# 56_ch_sample-and-hold_card_v1_0.net
KiCad netlist of a schematic drawn in EAGLE
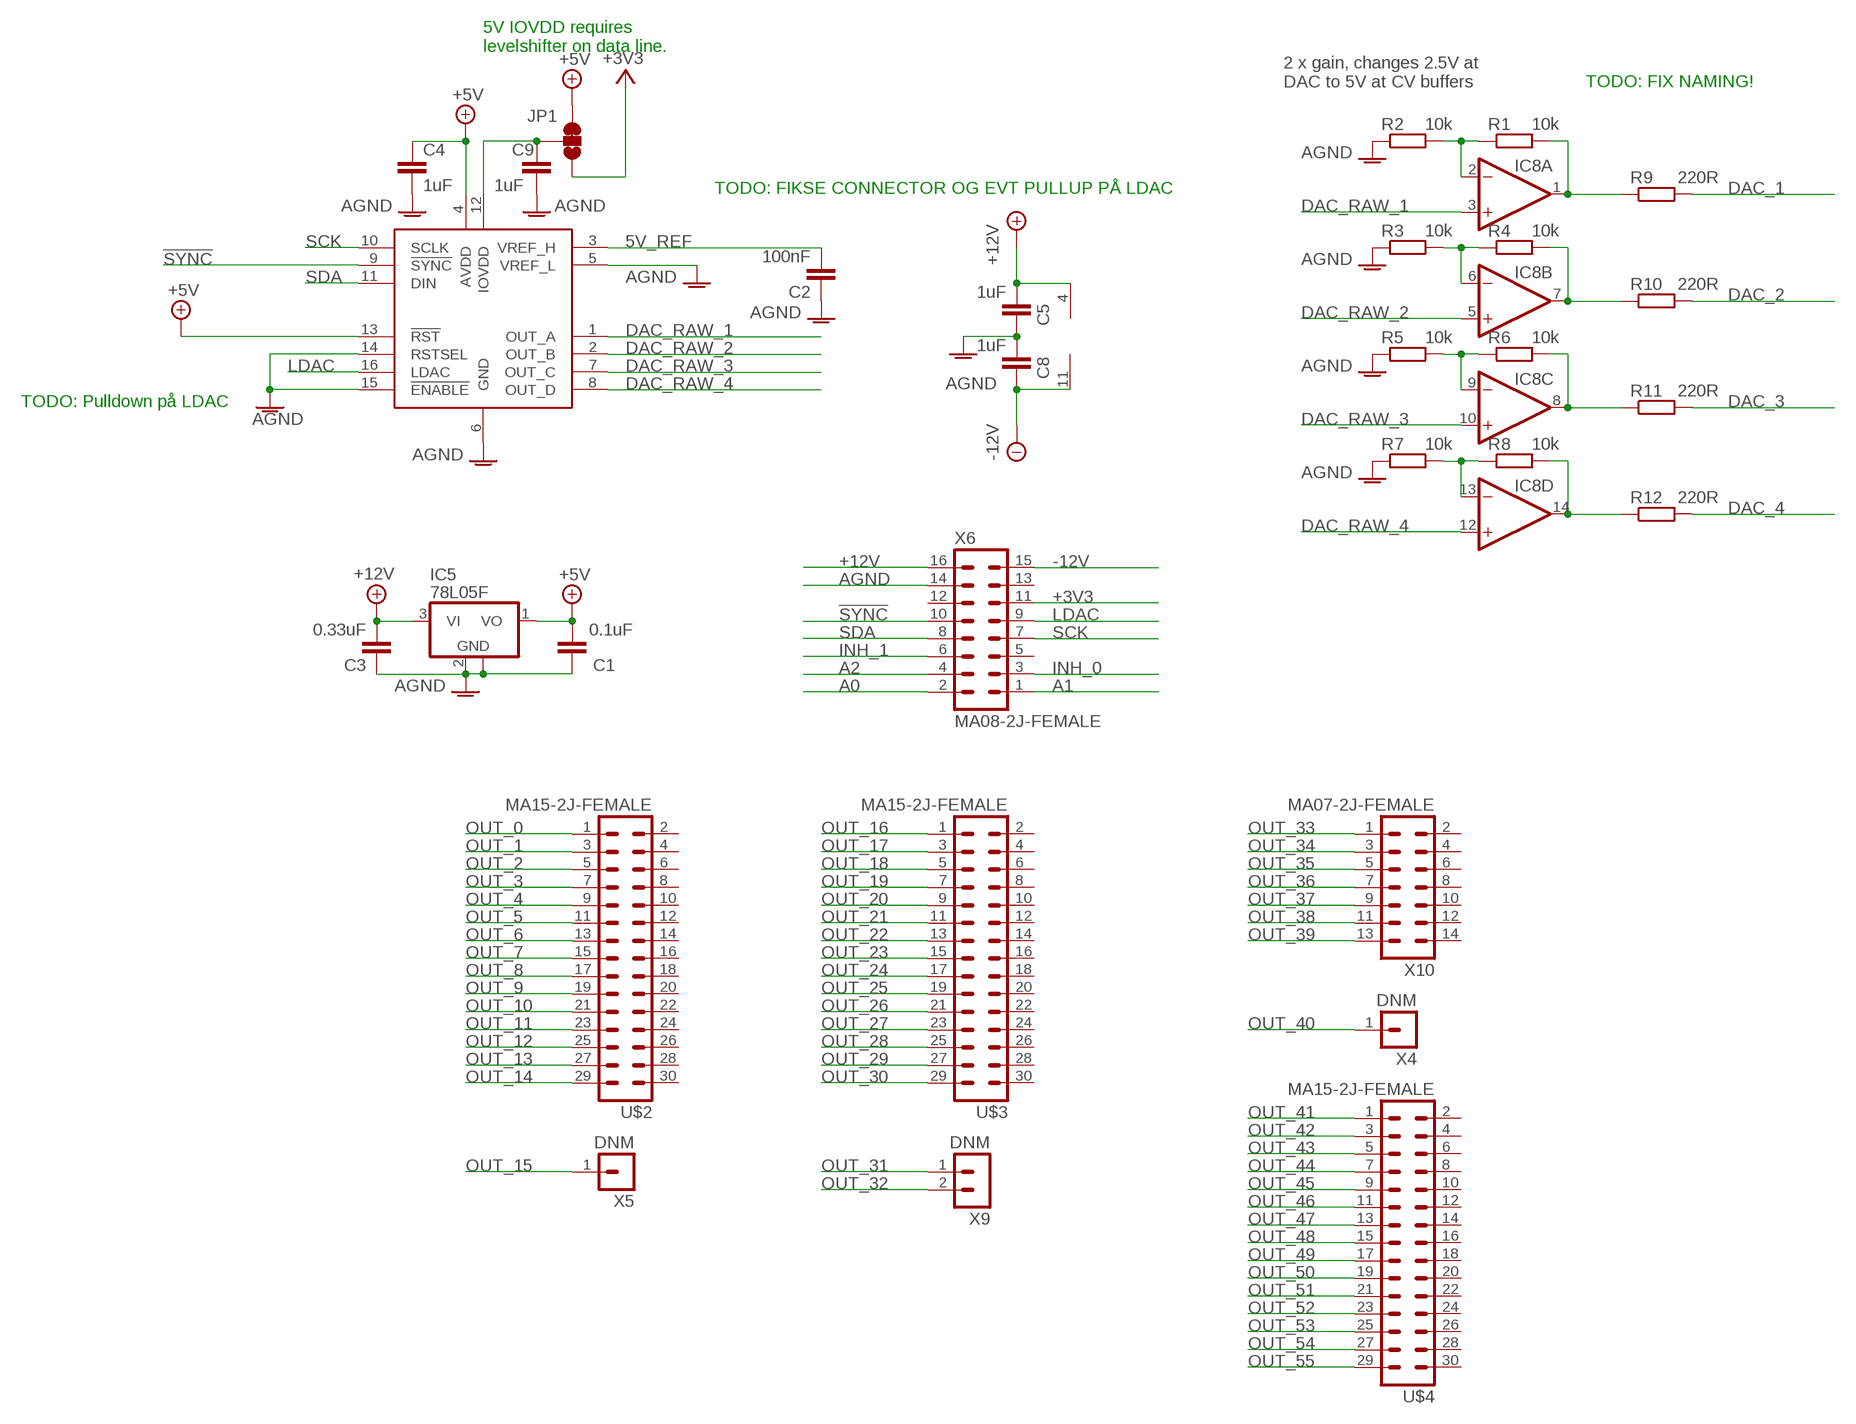
[diagram p0: schematic, sheet 1]
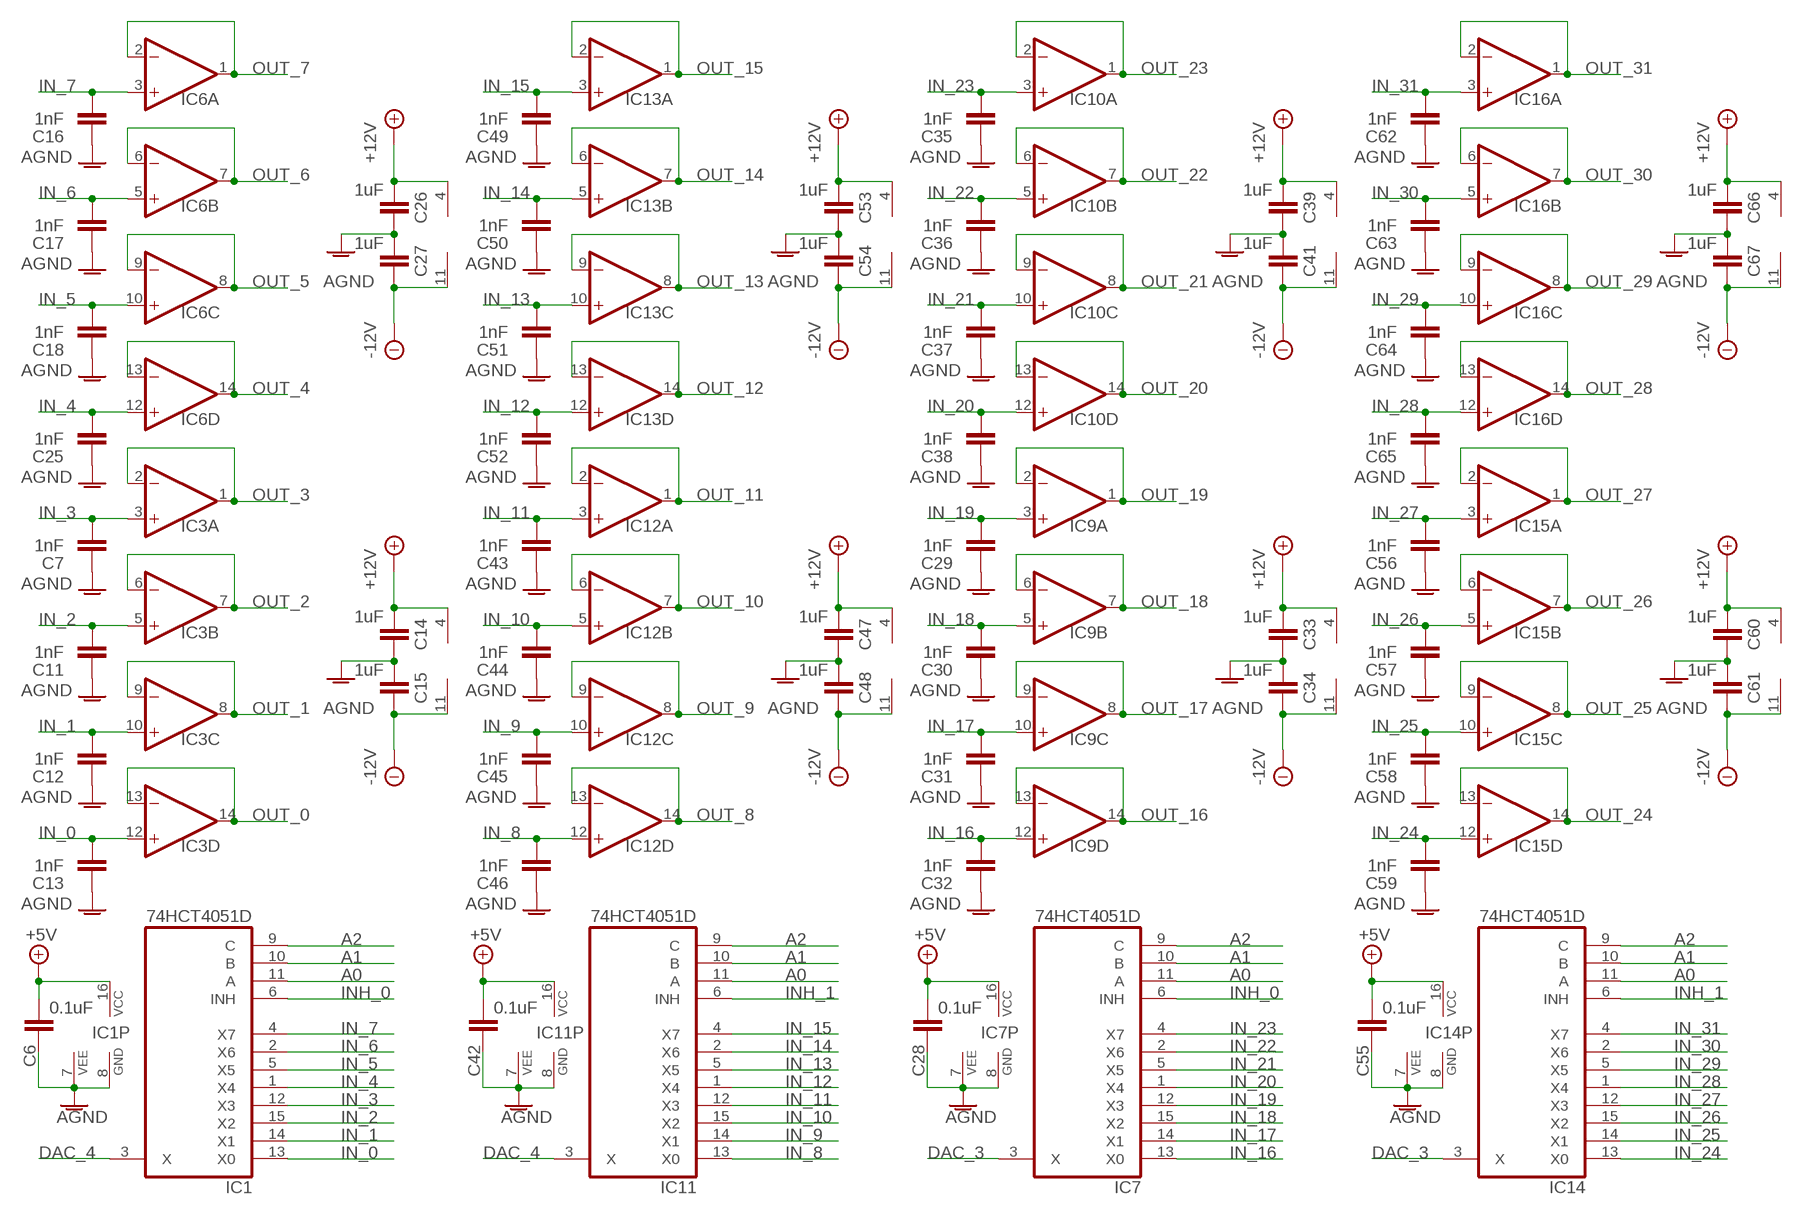
[diagram p1: schematic, sheet 2]
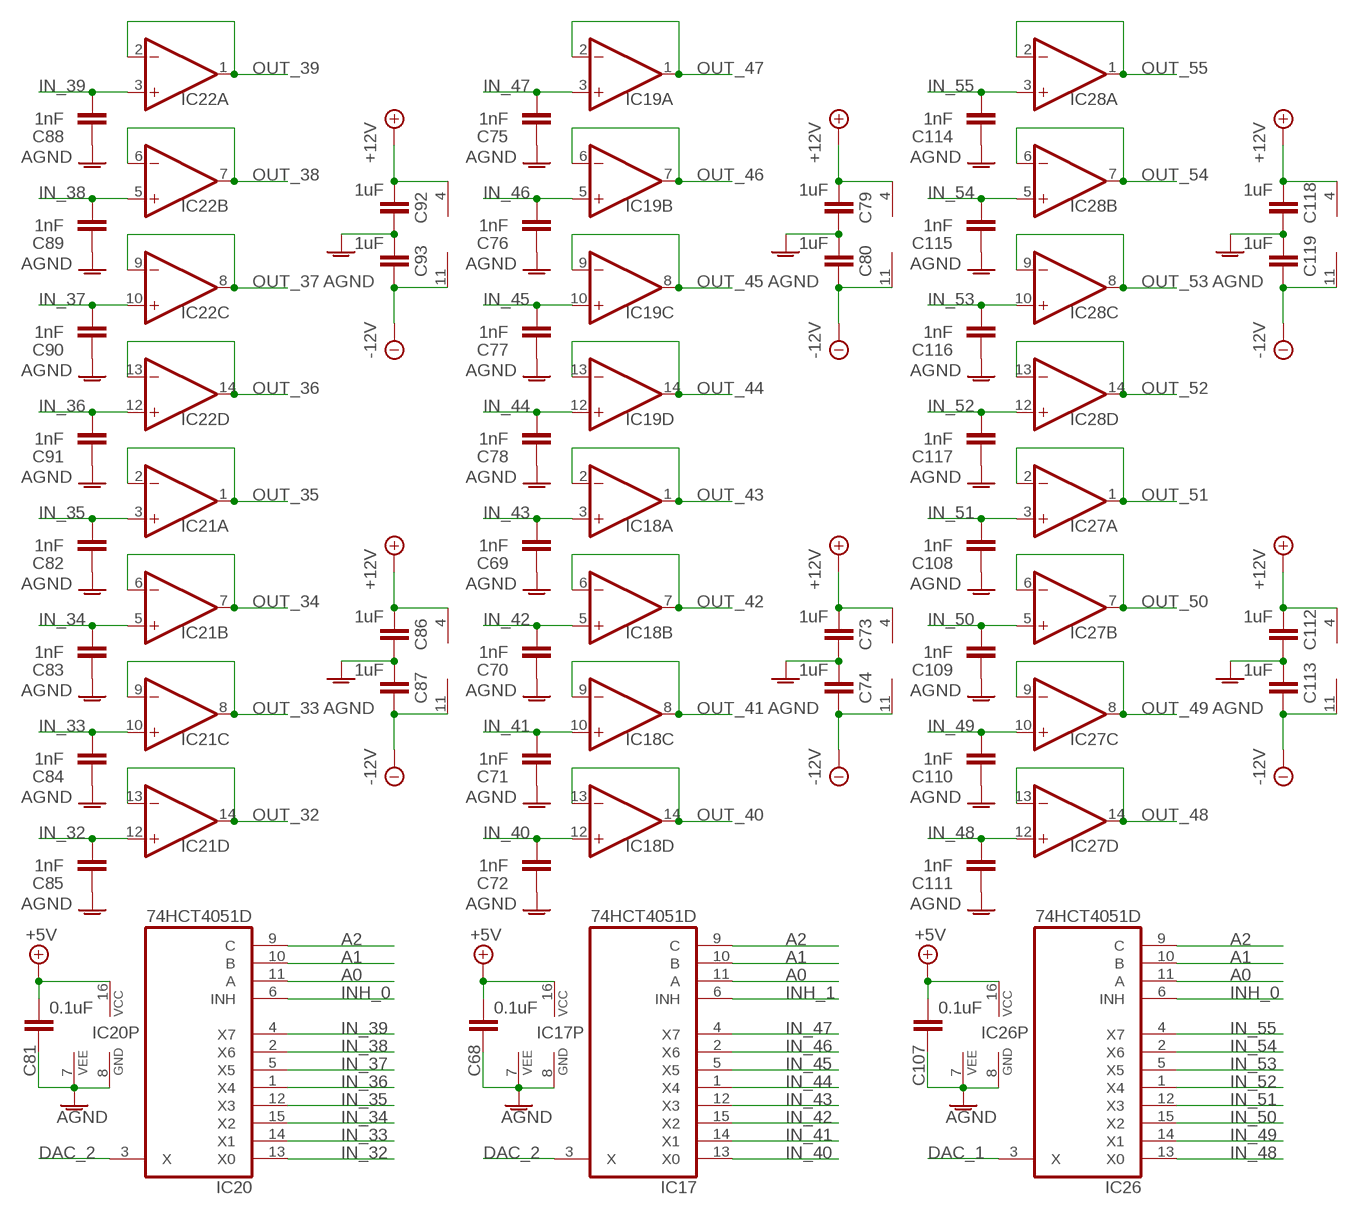
[diagram p2: schematic, sheet 3]

(export (version "E")
  (design (tool "Eeschema 10.0.6"))
  (components
    (comp (ref "C68")
      (value "0.1uF")
      (footprint "eagle-import:C0402-J")
      (libsource (lib "eagle-import") (part "C-EU-J0402"))
    )
    (comp (ref "C69")
      (value "1nF")
      (footprint "eagle-import:C0603-J")
      (libsource (lib "eagle-import") (part "C-EU-J0603"))
    )
    (comp (ref "C70")
      (value "1nF")
      (footprint "eagle-import:C0603-J")
      (libsource (lib "eagle-import") (part "C-EU-J0603"))
    )
    (comp (ref "C71")
      (value "1nF")
      (footprint "eagle-import:C0603-J")
      (libsource (lib "eagle-import") (part "C-EU-J0603"))
    )
    (comp (ref "C72")
      (value "1nF")
      (footprint "eagle-import:C0603-J")
      (libsource (lib "eagle-import") (part "C-EU-J0603"))
    )
    (comp (ref "C73")
      (value "1uF")
      (footprint "eagle-import:C0402-J")
      (libsource (lib "eagle-import") (part "C-EU-J0402"))
    )
    (comp (ref "C74")
      (value "1uF")
      (footprint "eagle-import:C0402-J")
      (libsource (lib "eagle-import") (part "C-EU-J0402"))
    )
    (comp (ref "C75")
      (value "1nF")
      (footprint "eagle-import:C0603-J")
      (libsource (lib "eagle-import") (part "C-EU-J0603"))
    )
    (comp (ref "C76")
      (value "1nF")
      (footprint "eagle-import:C0603-J")
      (libsource (lib "eagle-import") (part "C-EU-J0603"))
    )
    (comp (ref "C77")
      (value "1nF")
      (footprint "eagle-import:C0603-J")
      (libsource (lib "eagle-import") (part "C-EU-J0603"))
    )
    (comp (ref "C78")
      (value "1nF")
      (footprint "eagle-import:C0603-J")
      (libsource (lib "eagle-import") (part "C-EU-J0603"))
    )
    (comp (ref "C79")
      (value "1uF")
      (footprint "eagle-import:C0402-J")
      (libsource (lib "eagle-import") (part "C-EU-J0402"))
    )
    (comp (ref "C80")
      (value "1uF")
      (footprint "eagle-import:C0402-J")
      (libsource (lib "eagle-import") (part "C-EU-J0402"))
    )
    (comp (ref "C81")
      (value "0.1uF")
      (footprint "eagle-import:C0402-J")
      (libsource (lib "eagle-import") (part "C-EU-J0402"))
    )
    (comp (ref "C82")
      (value "1nF")
      (footprint "eagle-import:C0603-J")
      (libsource (lib "eagle-import") (part "C-EU-J0603"))
    )
    (comp (ref "C83")
      (value "1nF")
      (footprint "eagle-import:C0603-J")
      (libsource (lib "eagle-import") (part "C-EU-J0603"))
    )
    (comp (ref "C84")
      (value "1nF")
      (footprint "eagle-import:C0603-J")
      (libsource (lib "eagle-import") (part "C-EU-J0603"))
    )
    (comp (ref "C85")
      (value "1nF")
      (footprint "eagle-import:C0603-J")
      (libsource (lib "eagle-import") (part "C-EU-J0603"))
    )
    (comp (ref "C86")
      (value "1uF")
      (footprint "eagle-import:C0402-J")
      (libsource (lib "eagle-import") (part "C-EU-J0402"))
    )
    (comp (ref "C87")
      (value "1uF")
      (footprint "eagle-import:C0402-J")
      (libsource (lib "eagle-import") (part "C-EU-J0402"))
    )
    (comp (ref "C88")
      (value "1nF")
      (footprint "eagle-import:C0603-J")
      (libsource (lib "eagle-import") (part "C-EU-J0603"))
    )
    (comp (ref "C89")
      (value "1nF")
      (footprint "eagle-import:C0603-J")
      (libsource (lib "eagle-import") (part "C-EU-J0603"))
    )
    (comp (ref "C90")
      (value "1nF")
      (footprint "eagle-import:C0603-J")
      (libsource (lib "eagle-import") (part "C-EU-J0603"))
    )
    (comp (ref "C91")
      (value "1nF")
      (footprint "eagle-import:C0603-J")
      (libsource (lib "eagle-import") (part "C-EU-J0603"))
    )
    (comp (ref "C92")
      (value "1uF")
      (footprint "eagle-import:C0402-J")
      (libsource (lib "eagle-import") (part "C-EU-J0402"))
    )
    (comp (ref "C93")
      (value "1uF")
      (footprint "eagle-import:C0402-J")
      (libsource (lib "eagle-import") (part "C-EU-J0402"))
    )
    (comp (ref "C107")
      (value "0.1uF")
      (footprint "eagle-import:C0402-J")
      (libsource (lib "eagle-import") (part "C-EU-J0402"))
    )
    (comp (ref "C108")
      (value "1nF")
      (footprint "eagle-import:C0603-J")
      (libsource (lib "eagle-import") (part "C-EU-J0603"))
    )
    (comp (ref "C109")
      (value "1nF")
      (footprint "eagle-import:C0603-J")
      (libsource (lib "eagle-import") (part "C-EU-J0603"))
    )
    (comp (ref "C110")
      (value "1nF")
      (footprint "eagle-import:C0603-J")
      (libsource (lib "eagle-import") (part "C-EU-J0603"))
    )
    (comp (ref "C111")
      (value "1nF")
      (footprint "eagle-import:C0603-J")
      (libsource (lib "eagle-import") (part "C-EU-J0603"))
    )
    (comp (ref "C112")
      (value "1uF")
      (footprint "eagle-import:C0402-J")
      (libsource (lib "eagle-import") (part "C-EU-J0402"))
    )
    (comp (ref "C113")
      (value "1uF")
      (footprint "eagle-import:C0402-J")
      (libsource (lib "eagle-import") (part "C-EU-J0402"))
    )
    (comp (ref "C114")
      (value "1nF")
      (footprint "eagle-import:C0603-J")
      (libsource (lib "eagle-import") (part "C-EU-J0603"))
    )
    (comp (ref "C115")
      (value "1nF")
      (footprint "eagle-import:C0603-J")
      (libsource (lib "eagle-import") (part "C-EU-J0603"))
    )
    (comp (ref "C116")
      (value "1nF")
      (footprint "eagle-import:C0603-J")
      (libsource (lib "eagle-import") (part "C-EU-J0603"))
    )
    (comp (ref "C117")
      (value "1nF")
      (footprint "eagle-import:C0603-J")
      (libsource (lib "eagle-import") (part "C-EU-J0603"))
    )
    (comp (ref "C118")
      (value "1uF")
      (footprint "eagle-import:C0402-J")
      (libsource (lib "eagle-import") (part "C-EU-J0402"))
    )
    (comp (ref "C119")
      (value "1uF")
      (footprint "eagle-import:C0402-J")
      (libsource (lib "eagle-import") (part "C-EU-J0402"))
    )
    (comp (ref "IC17")
      (value "74HCT4051D")
      (footprint "eagle-import:SO16")
      (libsource (lib "eagle-import") (part "4051D"))
    )
    (comp (ref "IC18")
      (value "TL074JT")
      (footprint "eagle-import:TSSOP14J")
      (libsource (lib "eagle-import") (part "TL074JT"))
    )
    (comp (ref "IC19")
      (value "TL074JT")
      (footprint "eagle-import:TSSOP14J")
      (libsource (lib "eagle-import") (part "TL074JT"))
    )
    (comp (ref "IC20")
      (value "74HCT4051D")
      (footprint "eagle-import:SO16")
      (libsource (lib "eagle-import") (part "4051D"))
    )
    (comp (ref "IC21")
      (value "TL074JT")
      (footprint "eagle-import:TSSOP14J")
      (libsource (lib "eagle-import") (part "TL074JT"))
    )
    (comp (ref "IC22")
      (value "TL074JT")
      (footprint "eagle-import:TSSOP14J")
      (libsource (lib "eagle-import") (part "TL074JT"))
    )
    (comp (ref "IC26")
      (value "74HCT4051D")
      (footprint "eagle-import:SO16")
      (libsource (lib "eagle-import") (part "4051D"))
    )
    (comp (ref "IC27")
      (value "TL074JT")
      (footprint "eagle-import:TSSOP14J")
      (libsource (lib "eagle-import") (part "TL074JT"))
    )
    (comp (ref "IC28")
      (value "TL074JT")
      (footprint "eagle-import:TSSOP14J")
      (libsource (lib "eagle-import") (part "TL074JT"))
    )
    (comp (ref "C6")
      (value "0.1uF")
      (footprint "eagle-import:C0402-J")
      (libsource (lib "eagle-import") (part "C-EU-J0402"))
    )
    (comp (ref "C7")
      (value "1nF")
      (footprint "eagle-import:C0603-J")
      (libsource (lib "eagle-import") (part "C-EU-J0603"))
    )
    (comp (ref "C11")
      (value "1nF")
      (footprint "eagle-import:C0603-J")
      (libsource (lib "eagle-import") (part "C-EU-J0603"))
    )
    (comp (ref "C12")
      (value "1nF")
      (footprint "eagle-import:C0603-J")
      (libsource (lib "eagle-import") (part "C-EU-J0603"))
    )
    (comp (ref "C13")
      (value "1nF")
      (footprint "eagle-import:C0603-J")
      (libsource (lib "eagle-import") (part "C-EU-J0603"))
    )
    (comp (ref "C14")
      (value "1uF")
      (footprint "eagle-import:C0402-J")
      (libsource (lib "eagle-import") (part "C-EU-J0402"))
    )
    (comp (ref "C15")
      (value "1uF")
      (footprint "eagle-import:C0402-J")
      (libsource (lib "eagle-import") (part "C-EU-J0402"))
    )
    (comp (ref "C16")
      (value "1nF")
      (footprint "eagle-import:C0603-J")
      (libsource (lib "eagle-import") (part "C-EU-J0603"))
    )
    (comp (ref "C17")
      (value "1nF")
      (footprint "eagle-import:C0603-J")
      (libsource (lib "eagle-import") (part "C-EU-J0603"))
    )
    (comp (ref "C18")
      (value "1nF")
      (footprint "eagle-import:C0603-J")
      (libsource (lib "eagle-import") (part "C-EU-J0603"))
    )
    (comp (ref "C25")
      (value "1nF")
      (footprint "eagle-import:C0603-J")
      (libsource (lib "eagle-import") (part "C-EU-J0603"))
    )
    (comp (ref "C26")
      (value "1uF")
      (footprint "eagle-import:C0402-J")
      (libsource (lib "eagle-import") (part "C-EU-J0402"))
    )
    (comp (ref "C27")
      (value "1uF")
      (footprint "eagle-import:C0402-J")
      (libsource (lib "eagle-import") (part "C-EU-J0402"))
    )
    (comp (ref "C28")
      (value "0.1uF")
      (footprint "eagle-import:C0402-J")
      (libsource (lib "eagle-import") (part "C-EU-J0402"))
    )
    (comp (ref "C29")
      (value "1nF")
      (footprint "eagle-import:C0603-J")
      (libsource (lib "eagle-import") (part "C-EU-J0603"))
    )
    (comp (ref "C30")
      (value "1nF")
      (footprint "eagle-import:C0603-J")
      (libsource (lib "eagle-import") (part "C-EU-J0603"))
    )
    (comp (ref "C31")
      (value "1nF")
      (footprint "eagle-import:C0603-J")
      (libsource (lib "eagle-import") (part "C-EU-J0603"))
    )
    (comp (ref "C32")
      (value "1nF")
      (footprint "eagle-import:C0603-J")
      (libsource (lib "eagle-import") (part "C-EU-J0603"))
    )
    (comp (ref "C33")
      (value "1uF")
      (footprint "eagle-import:C0402-J")
      (libsource (lib "eagle-import") (part "C-EU-J0402"))
    )
    (comp (ref "C34")
      (value "1uF")
      (footprint "eagle-import:C0402-J")
      (libsource (lib "eagle-import") (part "C-EU-J0402"))
    )
    (comp (ref "C35")
      (value "1nF")
      (footprint "eagle-import:C0603-J")
      (libsource (lib "eagle-import") (part "C-EU-J0603"))
    )
    (comp (ref "C36")
      (value "1nF")
      (footprint "eagle-import:C0603-J")
      (libsource (lib "eagle-import") (part "C-EU-J0603"))
    )
    (comp (ref "C37")
      (value "1nF")
      (footprint "eagle-import:C0603-J")
      (libsource (lib "eagle-import") (part "C-EU-J0603"))
    )
    (comp (ref "C38")
      (value "1nF")
      (footprint "eagle-import:C0603-J")
      (libsource (lib "eagle-import") (part "C-EU-J0603"))
    )
    (comp (ref "C39")
      (value "1uF")
      (footprint "eagle-import:C0402-J")
      (libsource (lib "eagle-import") (part "C-EU-J0402"))
    )
    (comp (ref "C41")
      (value "1uF")
      (footprint "eagle-import:C0402-J")
      (libsource (lib "eagle-import") (part "C-EU-J0402"))
    )
    (comp (ref "C42")
      (value "0.1uF")
      (footprint "eagle-import:C0402-J")
      (libsource (lib "eagle-import") (part "C-EU-J0402"))
    )
    (comp (ref "C43")
      (value "1nF")
      (footprint "eagle-import:C0603-J")
      (libsource (lib "eagle-import") (part "C-EU-J0603"))
    )
    (comp (ref "C44")
      (value "1nF")
      (footprint "eagle-import:C0603-J")
      (libsource (lib "eagle-import") (part "C-EU-J0603"))
    )
    (comp (ref "C45")
      (value "1nF")
      (footprint "eagle-import:C0603-J")
      (libsource (lib "eagle-import") (part "C-EU-J0603"))
    )
    (comp (ref "C46")
      (value "1nF")
      (footprint "eagle-import:C0603-J")
      (libsource (lib "eagle-import") (part "C-EU-J0603"))
    )
    (comp (ref "C47")
      (value "1uF")
      (footprint "eagle-import:C0402-J")
      (libsource (lib "eagle-import") (part "C-EU-J0402"))
    )
    (comp (ref "C48")
      (value "1uF")
      (footprint "eagle-import:C0402-J")
      (libsource (lib "eagle-import") (part "C-EU-J0402"))
    )
    (comp (ref "C49")
      (value "1nF")
      (footprint "eagle-import:C0603-J")
      (libsource (lib "eagle-import") (part "C-EU-J0603"))
    )
    (comp (ref "C50")
      (value "1nF")
      (footprint "eagle-import:C0603-J")
      (libsource (lib "eagle-import") (part "C-EU-J0603"))
    )
    (comp (ref "C51")
      (value "1nF")
      (footprint "eagle-import:C0603-J")
      (libsource (lib "eagle-import") (part "C-EU-J0603"))
    )
    (comp (ref "C52")
      (value "1nF")
      (footprint "eagle-import:C0603-J")
      (libsource (lib "eagle-import") (part "C-EU-J0603"))
    )
    (comp (ref "C53")
      (value "1uF")
      (footprint "eagle-import:C0402-J")
      (libsource (lib "eagle-import") (part "C-EU-J0402"))
    )
    (comp (ref "C54")
      (value "1uF")
      (footprint "eagle-import:C0402-J")
      (libsource (lib "eagle-import") (part "C-EU-J0402"))
    )
    (comp (ref "C55")
      (value "0.1uF")
      (footprint "eagle-import:C0402-J")
      (libsource (lib "eagle-import") (part "C-EU-J0402"))
    )
    (comp (ref "C56")
      (value "1nF")
      (footprint "eagle-import:C0603-J")
      (libsource (lib "eagle-import") (part "C-EU-J0603"))
    )
    (comp (ref "C57")
      (value "1nF")
      (footprint "eagle-import:C0603-J")
      (libsource (lib "eagle-import") (part "C-EU-J0603"))
    )
    (comp (ref "C58")
      (value "1nF")
      (footprint "eagle-import:C0603-J")
      (libsource (lib "eagle-import") (part "C-EU-J0603"))
    )
    (comp (ref "C59")
      (value "1nF")
      (footprint "eagle-import:C0603-J")
      (libsource (lib "eagle-import") (part "C-EU-J0603"))
    )
    (comp (ref "C60")
      (value "1uF")
      (footprint "eagle-import:C0402-J")
      (libsource (lib "eagle-import") (part "C-EU-J0402"))
    )
    (comp (ref "C61")
      (value "1uF")
      (footprint "eagle-import:C0402-J")
      (libsource (lib "eagle-import") (part "C-EU-J0402"))
    )
    (comp (ref "C62")
      (value "1nF")
      (footprint "eagle-import:C0603-J")
      (libsource (lib "eagle-import") (part "C-EU-J0603"))
    )
    (comp (ref "C63")
      (value "1nF")
      (footprint "eagle-import:C0603-J")
      (libsource (lib "eagle-import") (part "C-EU-J0603"))
    )
    (comp (ref "C64")
      (value "1nF")
      (footprint "eagle-import:C0603-J")
      (libsource (lib "eagle-import") (part "C-EU-J0603"))
    )
    (comp (ref "C65")
      (value "1nF")
      (footprint "eagle-import:C0603-J")
      (libsource (lib "eagle-import") (part "C-EU-J0603"))
    )
    (comp (ref "C66")
      (value "1uF")
      (footprint "eagle-import:C0402-J")
      (libsource (lib "eagle-import") (part "C-EU-J0402"))
    )
    (comp (ref "C67")
      (value "1uF")
      (footprint "eagle-import:C0402-J")
      (libsource (lib "eagle-import") (part "C-EU-J0402"))
    )
    (comp (ref "IC1")
      (value "74HCT4051D")
      (footprint "eagle-import:SO16")
      (libsource (lib "eagle-import") (part "4051D"))
    )
    (comp (ref "IC3")
      (value "TL074JT")
      (footprint "eagle-import:TSSOP14J")
      (libsource (lib "eagle-import") (part "TL074JT"))
    )
    (comp (ref "IC6")
      (value "TL074JT")
      (footprint "eagle-import:TSSOP14J")
      (libsource (lib "eagle-import") (part "TL074JT"))
    )
    (comp (ref "IC7")
      (value "74HCT4051D")
      (footprint "eagle-import:SO16")
      (libsource (lib "eagle-import") (part "4051D"))
    )
    (comp (ref "IC9")
      (value "TL074JT")
      (footprint "eagle-import:TSSOP14J")
      (libsource (lib "eagle-import") (part "TL074JT"))
    )
    (comp (ref "IC10")
      (value "TL074JT")
      (footprint "eagle-import:TSSOP14J")
      (libsource (lib "eagle-import") (part "TL074JT"))
    )
    (comp (ref "IC11")
      (value "74HCT4051D")
      (footprint "eagle-import:SO16")
      (libsource (lib "eagle-import") (part "4051D"))
    )
    (comp (ref "IC12")
      (value "TL074JT")
      (footprint "eagle-import:TSSOP14J")
      (libsource (lib "eagle-import") (part "TL074JT"))
    )
    (comp (ref "IC13")
      (value "TL074JT")
      (footprint "eagle-import:TSSOP14J")
      (libsource (lib "eagle-import") (part "TL074JT"))
    )
    (comp (ref "IC14")
      (value "74HCT4051D")
      (footprint "eagle-import:SO16")
      (libsource (lib "eagle-import") (part "4051D"))
    )
    (comp (ref "IC15")
      (value "TL074JT")
      (footprint "eagle-import:TSSOP14J")
      (libsource (lib "eagle-import") (part "TL074JT"))
    )
    (comp (ref "IC16")
      (value "TL074JT")
      (footprint "eagle-import:TSSOP14J")
      (libsource (lib "eagle-import") (part "TL074JT"))
    )
    (comp (ref "C1")
      (value "0.1uF")
      (footprint "eagle-import:C0603")
      (libsource (lib "eagle-import") (part "C-EUC0603"))
    )
    (comp (ref "C2")
      (value "100nF")
      (footprint "eagle-import:C0603")
      (libsource (lib "eagle-import") (part "C-EUC0603"))
    )
    (comp (ref "C3")
      (value "0.33uF")
      (footprint "eagle-import:C0603")
      (libsource (lib "eagle-import") (part "C-EUC0603"))
    )
    (comp (ref "C4")
      (value "1uF")
      (footprint "eagle-import:C0402-J")
      (libsource (lib "eagle-import") (part "C-EU-J0402"))
    )
    (comp (ref "C5")
      (value "1uF")
      (footprint "eagle-import:C0402-J")
      (libsource (lib "eagle-import") (part "C-EU-J0402"))
    )
    (comp (ref "C8")
      (value "1uF")
      (footprint "eagle-import:C0402-J")
      (libsource (lib "eagle-import") (part "C-EU-J0402"))
    )
    (comp (ref "C9")
      (value "1uF")
      (footprint "eagle-import:C0402-J")
      (libsource (lib "eagle-import") (part "C-EU-J0402"))
    )
    (comp (ref "IC2")
      (value "DAC8565F")
      (footprint "eagle-import:DIL16-FM-CON")
      (libsource (lib "eagle-import") (part "DAC8565F"))
    )
    (comp (ref "IC5")
      (value "78L05F")
      (footprint "eagle-import:SOT89")
      (libsource (lib "eagle-import") (part "78LF05"))
    )
    (comp (ref "IC8")
      (value "TL074JT")
      (footprint "eagle-import:TSSOP14J")
      (libsource (lib "eagle-import") (part "TL074JT"))
    )
    (comp (ref "JP1")
      (value "JUMPER-SMT_3_1-NC_TRACE_NO-SILK_DNM")
      (footprint "eagle-import:SMT-JUMPER_3_1-NC_TRACE_NO-SILK")
      (libsource (lib "eagle-import") (part "JUMPER-SMT_3_1-NC_TRACE_NO-SILK"))
    )
    (comp (ref "R1")
      (value "10k")
      (footprint "eagle-import:R0603")
      (libsource (lib "eagle-import") (part "R-EU_R0603"))
    )
    (comp (ref "R2")
      (value "10k")
      (footprint "eagle-import:R0603")
      (libsource (lib "eagle-import") (part "R-EU_R0603"))
    )
    (comp (ref "R3")
      (value "10k")
      (footprint "eagle-import:R0603")
      (libsource (lib "eagle-import") (part "R-EU_R0603"))
    )
    (comp (ref "R4")
      (value "10k")
      (footprint "eagle-import:R0603")
      (libsource (lib "eagle-import") (part "R-EU_R0603"))
    )
    (comp (ref "R5")
      (value "10k")
      (footprint "eagle-import:R0603")
      (libsource (lib "eagle-import") (part "R-EU_R0603"))
    )
    (comp (ref "R6")
      (value "10k")
      (footprint "eagle-import:R0603")
      (libsource (lib "eagle-import") (part "R-EU_R0603"))
    )
    (comp (ref "R7")
      (value "10k")
      (footprint "eagle-import:R0603")
      (libsource (lib "eagle-import") (part "R-EU_R0603"))
    )
    (comp (ref "R8")
      (value "10k")
      (footprint "eagle-import:R0603")
      (libsource (lib "eagle-import") (part "R-EU_R0603"))
    )
    (comp (ref "R9")
      (value "220R")
      (footprint "eagle-import:R0603")
      (libsource (lib "eagle-import") (part "R-EU_R0603"))
    )
    (comp (ref "R10")
      (value "220R")
      (footprint "eagle-import:R0603")
      (libsource (lib "eagle-import") (part "R-EU_R0603"))
    )
    (comp (ref "R11")
      (value "220R")
      (footprint "eagle-import:R0603")
      (libsource (lib "eagle-import") (part "R-EU_R0603"))
    )
    (comp (ref "R12")
      (value "220R")
      (footprint "eagle-import:R0603")
      (libsource (lib "eagle-import") (part "R-EU_R0603"))
    )
    (comp (ref "U$2")
      (value "MA15-2J-FEMALE")
      (footprint "eagle-import:MA15-2J")
      (libsource (lib "eagle-import") (part "MA15-2J"))
    )
    (comp (ref "U$3")
      (value "MA15-2J-FEMALE")
      (footprint "eagle-import:MA15-2J")
      (libsource (lib "eagle-import") (part "MA15-2J"))
    )
    (comp (ref "U$4")
      (value "MA15-2J-FEMALE")
      (footprint "eagle-import:MA15-2J")
      (libsource (lib "eagle-import") (part "MA15-2J"))
    )
    (comp (ref "X4")
      (value "DNM")
      (footprint "eagle-import:MA01N-1J")
      (libsource (lib "eagle-import") (part "MA01-1JN"))
    )
    (comp (ref "X5")
      (value "DNM")
      (footprint "eagle-import:MA01N-1J")
      (libsource (lib "eagle-import") (part "MA01-1JN"))
    )
    (comp (ref "X6")
      (value "MA08-2J-FEMALE")
      (footprint "eagle-import:MA08-2J")
      (libsource (lib "eagle-import") (part "MA08-2J"))
    )
    (comp (ref "X9")
      (value "DNM")
      (footprint "eagle-import:MA02N-1J")
      (libsource (lib "eagle-import") (part "MA02-1JN"))
    )
    (comp (ref "X10")
      (value "MA07-2J-FEMALE")
      (footprint "eagle-import:MA07-2J")
      (libsource (lib "eagle-import") (part "MA07-2J"))
    )
  )
  (nets
    (net (code "1") (name "+3V3") (class "Default")
      (node (ref "JP1") (pin "1") (pinfunction "1_1") (pintype "passive"))
      (node (ref "X6") (pin "11") (pinfunction "11_11") (pintype "passive"))
    )
    (net (code "2") (name "+5V") (class "Default")
      (node (ref "C1") (pin "2") (pinfunction "2_2") (pintype "passive"))
      (node (ref "C107") (pin "2") (pinfunction "2_2") (pintype "passive"))
      (node (ref "C28") (pin "2") (pinfunction "2_2") (pintype "passive"))
      (node (ref "C4") (pin "1") (pinfunction "1_1") (pintype "passive"))
      (node (ref "C42") (pin "2") (pinfunction "2_2") (pintype "passive"))
      (node (ref "C55") (pin "2") (pinfunction "2_2") (pintype "passive"))
      (node (ref "C6") (pin "2") (pinfunction "2_2") (pintype "passive"))
      (node (ref "C68") (pin "2") (pinfunction "2_2") (pintype "passive"))
      (node (ref "C81") (pin "2") (pinfunction "2_2") (pintype "passive"))
      (node (ref "IC1") (pin "16") (pinfunction "VCC_16") (pintype "power_in"))
      (node (ref "IC11") (pin "16") (pinfunction "VCC_16") (pintype "power_in"))
      (node (ref "IC14") (pin "16") (pinfunction "VCC_16") (pintype "power_in"))
      (node (ref "IC17") (pin "16") (pinfunction "VCC_16") (pintype "power_in"))
      (node (ref "IC2") (pin "13") (pinfunction "~{RST}_13") (pintype "bidirectional"))
      (node (ref "IC2") (pin "4") (pinfunction "AVDD_4") (pintype "power_in"))
      (node (ref "IC20") (pin "16") (pinfunction "VCC_16") (pintype "power_in"))
      (node (ref "IC26") (pin "16") (pinfunction "VCC_16") (pintype "power_in"))
      (node (ref "IC5") (pin "1") (pinfunction "VO_1") (pintype "passive"))
      (node (ref "IC7") (pin "16") (pinfunction "VCC_16") (pintype "power_in"))
      (node (ref "JP1") (pin "3") (pinfunction "3_3") (pintype "passive"))
    )
    (net (code "3") (name "+12V") (class "Default")
      (node (ref "C112") (pin "1") (pinfunction "1_1") (pintype "passive"))
      (node (ref "C118") (pin "1") (pinfunction "1_1") (pintype "passive"))
      (node (ref "C14") (pin "1") (pinfunction "1_1") (pintype "passive"))
      (node (ref "C26") (pin "1") (pinfunction "1_1") (pintype "passive"))
      (node (ref "C3") (pin "2") (pinfunction "2_2") (pintype "passive"))
      (node (ref "C33") (pin "1") (pinfunction "1_1") (pintype "passive"))
      (node (ref "C39") (pin "1") (pinfunction "1_1") (pintype "passive"))
      (node (ref "C47") (pin "1") (pinfunction "1_1") (pintype "passive"))
      (node (ref "C5") (pin "1") (pinfunction "1_1") (pintype "passive"))
      (node (ref "C53") (pin "1") (pinfunction "1_1") (pintype "passive"))
      (node (ref "C60") (pin "1") (pinfunction "1_1") (pintype "passive"))
      (node (ref "C66") (pin "1") (pinfunction "1_1") (pintype "passive"))
      (node (ref "C73") (pin "1") (pinfunction "1_1") (pintype "passive"))
      (node (ref "C79") (pin "1") (pinfunction "1_1") (pintype "passive"))
      (node (ref "C86") (pin "1") (pinfunction "1_1") (pintype "passive"))
      (node (ref "C92") (pin "1") (pinfunction "1_1") (pintype "passive"))
      (node (ref "IC10") (pin "4") (pinfunction "V+_4") (pintype "power_in"))
      (node (ref "IC12") (pin "4") (pinfunction "V+_4") (pintype "power_in"))
      (node (ref "IC13") (pin "4") (pinfunction "V+_4") (pintype "power_in"))
      (node (ref "IC15") (pin "4") (pinfunction "V+_4") (pintype "power_in"))
      (node (ref "IC16") (pin "4") (pinfunction "V+_4") (pintype "power_in"))
      (node (ref "IC18") (pin "4") (pinfunction "V+_4") (pintype "power_in"))
      (node (ref "IC19") (pin "4") (pinfunction "V+_4") (pintype "power_in"))
      (node (ref "IC21") (pin "4") (pinfunction "V+_4") (pintype "power_in"))
      (node (ref "IC22") (pin "4") (pinfunction "V+_4") (pintype "power_in"))
      (node (ref "IC27") (pin "4") (pinfunction "V+_4") (pintype "power_in"))
      (node (ref "IC28") (pin "4") (pinfunction "V+_4") (pintype "power_in"))
      (node (ref "IC3") (pin "4") (pinfunction "V+_4") (pintype "power_in"))
      (node (ref "IC5") (pin "3") (pinfunction "VI_3") (pintype "input"))
      (node (ref "IC6") (pin "4") (pinfunction "V+_4") (pintype "power_in"))
      (node (ref "IC8") (pin "4") (pinfunction "V+_4") (pintype "power_in"))
      (node (ref "IC9") (pin "4") (pinfunction "V+_4") (pintype "power_in"))
      (node (ref "X6") (pin "16") (pinfunction "16_16") (pintype "passive"))
    )
    (net (code "4") (name "-12V") (class "Default")
      (node (ref "C113") (pin "2") (pinfunction "2_2") (pintype "passive"))
      (node (ref "C119") (pin "2") (pinfunction "2_2") (pintype "passive"))
      (node (ref "C15") (pin "2") (pinfunction "2_2") (pintype "passive"))
      (node (ref "C27") (pin "2") (pinfunction "2_2") (pintype "passive"))
      (node (ref "C34") (pin "2") (pinfunction "2_2") (pintype "passive"))
      (node (ref "C41") (pin "2") (pinfunction "2_2") (pintype "passive"))
      (node (ref "C48") (pin "2") (pinfunction "2_2") (pintype "passive"))
      (node (ref "C54") (pin "2") (pinfunction "2_2") (pintype "passive"))
      (node (ref "C61") (pin "2") (pinfunction "2_2") (pintype "passive"))
      (node (ref "C67") (pin "2") (pinfunction "2_2") (pintype "passive"))
      (node (ref "C74") (pin "2") (pinfunction "2_2") (pintype "passive"))
      (node (ref "C8") (pin "2") (pinfunction "2_2") (pintype "passive"))
      (node (ref "C80") (pin "2") (pinfunction "2_2") (pintype "passive"))
      (node (ref "C87") (pin "2") (pinfunction "2_2") (pintype "passive"))
      (node (ref "C93") (pin "2") (pinfunction "2_2") (pintype "passive"))
      (node (ref "IC10") (pin "11") (pinfunction "V-_11") (pintype "power_in"))
      (node (ref "IC12") (pin "11") (pinfunction "V-_11") (pintype "power_in"))
      (node (ref "IC13") (pin "11") (pinfunction "V-_11") (pintype "power_in"))
      (node (ref "IC15") (pin "11") (pinfunction "V-_11") (pintype "power_in"))
      (node (ref "IC16") (pin "11") (pinfunction "V-_11") (pintype "power_in"))
      (node (ref "IC18") (pin "11") (pinfunction "V-_11") (pintype "power_in"))
      (node (ref "IC19") (pin "11") (pinfunction "V-_11") (pintype "power_in"))
      (node (ref "IC21") (pin "11") (pinfunction "V-_11") (pintype "power_in"))
      (node (ref "IC22") (pin "11") (pinfunction "V-_11") (pintype "power_in"))
      (node (ref "IC27") (pin "11") (pinfunction "V-_11") (pintype "power_in"))
      (node (ref "IC28") (pin "11") (pinfunction "V-_11") (pintype "power_in"))
      (node (ref "IC3") (pin "11") (pinfunction "V-_11") (pintype "power_in"))
      (node (ref "IC6") (pin "11") (pinfunction "V-_11") (pintype "power_in"))
      (node (ref "IC8") (pin "11") (pinfunction "V-_11") (pintype "power_in"))
      (node (ref "IC9") (pin "11") (pinfunction "V-_11") (pintype "power_in"))
      (node (ref "X6") (pin "15") (pinfunction "15_15") (pintype "passive"))
    )
    (net (code "5") (name "5V_REF") (class "Default")
      (node (ref "C2") (pin "2") (pinfunction "2_2") (pintype "passive"))
      (node (ref "IC2") (pin "3") (pinfunction "VREF_H_3") (pintype "bidirectional"))
    )
    (net (code "6") (name "A0") (class "Default")
      (node (ref "IC1") (pin "11") (pinfunction "A_11") (pintype "input"))
      (node (ref "IC11") (pin "11") (pinfunction "A_11") (pintype "input"))
      (node (ref "IC14") (pin "11") (pinfunction "A_11") (pintype "input"))
      (node (ref "IC17") (pin "11") (pinfunction "A_11") (pintype "input"))
      (node (ref "IC20") (pin "11") (pinfunction "A_11") (pintype "input"))
      (node (ref "IC26") (pin "11") (pinfunction "A_11") (pintype "input"))
      (node (ref "IC7") (pin "11") (pinfunction "A_11") (pintype "input"))
      (node (ref "X6") (pin "2") (pinfunction "2_2") (pintype "passive"))
    )
    (net (code "7") (name "A1") (class "Default")
      (node (ref "IC1") (pin "10") (pinfunction "B_10") (pintype "input"))
      (node (ref "IC11") (pin "10") (pinfunction "B_10") (pintype "input"))
      (node (ref "IC14") (pin "10") (pinfunction "B_10") (pintype "input"))
      (node (ref "IC17") (pin "10") (pinfunction "B_10") (pintype "input"))
      (node (ref "IC20") (pin "10") (pinfunction "B_10") (pintype "input"))
      (node (ref "IC26") (pin "10") (pinfunction "B_10") (pintype "input"))
      (node (ref "IC7") (pin "10") (pinfunction "B_10") (pintype "input"))
      (node (ref "X6") (pin "1") (pinfunction "1_1") (pintype "passive"))
    )
    (net (code "8") (name "A2") (class "Default")
      (node (ref "IC1") (pin "9") (pinfunction "C_9") (pintype "input"))
      (node (ref "IC11") (pin "9") (pinfunction "C_9") (pintype "input"))
      (node (ref "IC14") (pin "9") (pinfunction "C_9") (pintype "input"))
      (node (ref "IC17") (pin "9") (pinfunction "C_9") (pintype "input"))
      (node (ref "IC20") (pin "9") (pinfunction "C_9") (pintype "input"))
      (node (ref "IC26") (pin "9") (pinfunction "C_9") (pintype "input"))
      (node (ref "IC7") (pin "9") (pinfunction "C_9") (pintype "input"))
      (node (ref "X6") (pin "4") (pinfunction "4_4") (pintype "passive"))
    )
    (net (code "9") (name "AGND") (class "Default")
      (node (ref "C1") (pin "1") (pinfunction "1_1") (pintype "passive"))
      (node (ref "C107") (pin "1") (pinfunction "1_1") (pintype "passive"))
      (node (ref "C108") (pin "1") (pinfunction "1_1") (pintype "passive"))
      (node (ref "C109") (pin "1") (pinfunction "1_1") (pintype "passive"))
      (node (ref "C11") (pin "1") (pinfunction "1_1") (pintype "passive"))
      (node (ref "C110") (pin "1") (pinfunction "1_1") (pintype "passive"))
      (node (ref "C111") (pin "1") (pinfunction "1_1") (pintype "passive"))
      (node (ref "C112") (pin "2") (pinfunction "2_2") (pintype "passive"))
      (node (ref "C113") (pin "1") (pinfunction "1_1") (pintype "passive"))
      (node (ref "C114") (pin "1") (pinfunction "1_1") (pintype "passive"))
      (node (ref "C115") (pin "1") (pinfunction "1_1") (pintype "passive"))
      (node (ref "C116") (pin "1") (pinfunction "1_1") (pintype "passive"))
      (node (ref "C117") (pin "1") (pinfunction "1_1") (pintype "passive"))
      (node (ref "C118") (pin "2") (pinfunction "2_2") (pintype "passive"))
      (node (ref "C119") (pin "1") (pinfunction "1_1") (pintype "passive"))
      (node (ref "C12") (pin "1") (pinfunction "1_1") (pintype "passive"))
      (node (ref "C13") (pin "1") (pinfunction "1_1") (pintype "passive"))
      (node (ref "C14") (pin "2") (pinfunction "2_2") (pintype "passive"))
      (node (ref "C15") (pin "1") (pinfunction "1_1") (pintype "passive"))
      (node (ref "C16") (pin "1") (pinfunction "1_1") (pintype "passive"))
      (node (ref "C17") (pin "1") (pinfunction "1_1") (pintype "passive"))
      (node (ref "C18") (pin "1") (pinfunction "1_1") (pintype "passive"))
      (node (ref "C2") (pin "1") (pinfunction "1_1") (pintype "passive"))
      (node (ref "C25") (pin "1") (pinfunction "1_1") (pintype "passive"))
      (node (ref "C26") (pin "2") (pinfunction "2_2") (pintype "passive"))
      (node (ref "C27") (pin "1") (pinfunction "1_1") (pintype "passive"))
      (node (ref "C28") (pin "1") (pinfunction "1_1") (pintype "passive"))
      (node (ref "C29") (pin "1") (pinfunction "1_1") (pintype "passive"))
      (node (ref "C3") (pin "1") (pinfunction "1_1") (pintype "passive"))
      (node (ref "C30") (pin "1") (pinfunction "1_1") (pintype "passive"))
      (node (ref "C31") (pin "1") (pinfunction "1_1") (pintype "passive"))
      (node (ref "C32") (pin "1") (pinfunction "1_1") (pintype "passive"))
      (node (ref "C33") (pin "2") (pinfunction "2_2") (pintype "passive"))
      (node (ref "C34") (pin "1") (pinfunction "1_1") (pintype "passive"))
      (node (ref "C35") (pin "1") (pinfunction "1_1") (pintype "passive"))
      (node (ref "C36") (pin "1") (pinfunction "1_1") (pintype "passive"))
      (node (ref "C37") (pin "1") (pinfunction "1_1") (pintype "passive"))
      (node (ref "C38") (pin "1") (pinfunction "1_1") (pintype "passive"))
      (node (ref "C39") (pin "2") (pinfunction "2_2") (pintype "passive"))
      (node (ref "C4") (pin "2") (pinfunction "2_2") (pintype "passive"))
      (node (ref "C41") (pin "1") (pinfunction "1_1") (pintype "passive"))
      (node (ref "C42") (pin "1") (pinfunction "1_1") (pintype "passive"))
      (node (ref "C43") (pin "1") (pinfunction "1_1") (pintype "passive"))
      (node (ref "C44") (pin "1") (pinfunction "1_1") (pintype "passive"))
      (node (ref "C45") (pin "1") (pinfunction "1_1") (pintype "passive"))
      (node (ref "C46") (pin "1") (pinfunction "1_1") (pintype "passive"))
      (node (ref "C47") (pin "2") (pinfunction "2_2") (pintype "passive"))
      (node (ref "C48") (pin "1") (pinfunction "1_1") (pintype "passive"))
      (node (ref "C49") (pin "1") (pinfunction "1_1") (pintype "passive"))
      (node (ref "C5") (pin "2") (pinfunction "2_2") (pintype "passive"))
      (node (ref "C50") (pin "1") (pinfunction "1_1") (pintype "passive"))
      (node (ref "C51") (pin "1") (pinfunction "1_1") (pintype "passive"))
      (node (ref "C52") (pin "1") (pinfunction "1_1") (pintype "passive"))
      (node (ref "C53") (pin "2") (pinfunction "2_2") (pintype "passive"))
      (node (ref "C54") (pin "1") (pinfunction "1_1") (pintype "passive"))
      (node (ref "C55") (pin "1") (pinfunction "1_1") (pintype "passive"))
      (node (ref "C56") (pin "1") (pinfunction "1_1") (pintype "passive"))
      (node (ref "C57") (pin "1") (pinfunction "1_1") (pintype "passive"))
      (node (ref "C58") (pin "1") (pinfunction "1_1") (pintype "passive"))
      (node (ref "C59") (pin "1") (pinfunction "1_1") (pintype "passive"))
      (node (ref "C6") (pin "1") (pinfunction "1_1") (pintype "passive"))
      (node (ref "C60") (pin "2") (pinfunction "2_2") (pintype "passive"))
      (node (ref "C61") (pin "1") (pinfunction "1_1") (pintype "passive"))
      (node (ref "C62") (pin "1") (pinfunction "1_1") (pintype "passive"))
      (node (ref "C63") (pin "1") (pinfunction "1_1") (pintype "passive"))
      (node (ref "C64") (pin "1") (pinfunction "1_1") (pintype "passive"))
      (node (ref "C65") (pin "1") (pinfunction "1_1") (pintype "passive"))
      (node (ref "C66") (pin "2") (pinfunction "2_2") (pintype "passive"))
      (node (ref "C67") (pin "1") (pinfunction "1_1") (pintype "passive"))
      (node (ref "C68") (pin "1") (pinfunction "1_1") (pintype "passive"))
      (node (ref "C69") (pin "1") (pinfunction "1_1") (pintype "passive"))
      (node (ref "C7") (pin "1") (pinfunction "1_1") (pintype "passive"))
      (node (ref "C70") (pin "1") (pinfunction "1_1") (pintype "passive"))
      (node (ref "C71") (pin "1") (pinfunction "1_1") (pintype "passive"))
      (node (ref "C72") (pin "1") (pinfunction "1_1") (pintype "passive"))
      (node (ref "C73") (pin "2") (pinfunction "2_2") (pintype "passive"))
      (node (ref "C74") (pin "1") (pinfunction "1_1") (pintype "passive"))
      (node (ref "C75") (pin "1") (pinfunction "1_1") (pintype "passive"))
      (node (ref "C76") (pin "1") (pinfunction "1_1") (pintype "passive"))
      (node (ref "C77") (pin "1") (pinfunction "1_1") (pintype "passive"))
      (node (ref "C78") (pin "1") (pinfunction "1_1") (pintype "passive"))
      (node (ref "C79") (pin "2") (pinfunction "2_2") (pintype "passive"))
      (node (ref "C8") (pin "1") (pinfunction "1_1") (pintype "passive"))
      (node (ref "C80") (pin "1") (pinfunction "1_1") (pintype "passive"))
      (node (ref "C81") (pin "1") (pinfunction "1_1") (pintype "passive"))
      (node (ref "C82") (pin "1") (pinfunction "1_1") (pintype "passive"))
      (node (ref "C83") (pin "1") (pinfunction "1_1") (pintype "passive"))
      (node (ref "C84") (pin "1") (pinfunction "1_1") (pintype "passive"))
      (node (ref "C85") (pin "1") (pinfunction "1_1") (pintype "passive"))
      (node (ref "C86") (pin "2") (pinfunction "2_2") (pintype "passive"))
      (node (ref "C87") (pin "1") (pinfunction "1_1") (pintype "passive"))
      (node (ref "C88") (pin "1") (pinfunction "1_1") (pintype "passive"))
      (node (ref "C89") (pin "1") (pinfunction "1_1") (pintype "passive"))
      (node (ref "C9") (pin "2") (pinfunction "2_2") (pintype "passive"))
      (node (ref "C90") (pin "1") (pinfunction "1_1") (pintype "passive"))
      (node (ref "C91") (pin "1") (pinfunction "1_1") (pintype "passive"))
      (node (ref "C92") (pin "2") (pinfunction "2_2") (pintype "passive"))
      (node (ref "C93") (pin "1") (pinfunction "1_1") (pintype "passive"))
      (node (ref "IC1") (pin "7") (pinfunction "VEE_7") (pintype "power_in"))
      (node (ref "IC1") (pin "8") (pinfunction "GND_8") (pintype "power_in"))
      (node (ref "IC11") (pin "7") (pinfunction "VEE_7") (pintype "power_in"))
      (node (ref "IC11") (pin "8") (pinfunction "GND_8") (pintype "power_in"))
      (node (ref "IC14") (pin "7") (pinfunction "VEE_7") (pintype "power_in"))
      (node (ref "IC14") (pin "8") (pinfunction "GND_8") (pintype "power_in"))
      (node (ref "IC17") (pin "7") (pinfunction "VEE_7") (pintype "power_in"))
      (node (ref "IC17") (pin "8") (pinfunction "GND_8") (pintype "power_in"))
      (node (ref "IC2") (pin "14") (pinfunction "RSTSEL_14") (pintype "bidirectional"))
      (node (ref "IC2") (pin "15") (pinfunction "~{ENABLE}_15") (pintype "bidirectional"))
      (node (ref "IC2") (pin "5") (pinfunction "VREF_L_5") (pintype "bidirectional"))
      (node (ref "IC2") (pin "6") (pinfunction "GND_6") (pintype "bidirectional"))
      (node (ref "IC20") (pin "7") (pinfunction "VEE_7") (pintype "power_in"))
      (node (ref "IC20") (pin "8") (pinfunction "GND_8") (pintype "power_in"))
      (node (ref "IC26") (pin "7") (pinfunction "VEE_7") (pintype "power_in"))
      (node (ref "IC26") (pin "8") (pinfunction "GND_8") (pintype "power_in"))
      (node (ref "IC5") (pin "2") (pinfunction "GND_2") (pintype "passive"))
      (node (ref "IC5") (pin "2@1") (pinfunction "GND_2@1") (pintype "passive"))
      (node (ref "IC7") (pin "7") (pinfunction "VEE_7") (pintype "power_in"))
      (node (ref "IC7") (pin "8") (pinfunction "GND_8") (pintype "power_in"))
      (node (ref "R2") (pin "1") (pinfunction "1_1") (pintype "passive"))
      (node (ref "R3") (pin "1") (pinfunction "1_1") (pintype "passive"))
      (node (ref "R5") (pin "1") (pinfunction "1_1") (pintype "passive"))
      (node (ref "R7") (pin "1") (pinfunction "1_1") (pintype "passive"))
      (node (ref "X6") (pin "14") (pinfunction "14_14") (pintype "passive"))
    )
    (net (code "10") (name "DAC_1") (class "Default")
      (node (ref "IC26") (pin "3") (pinfunction "X_3") (pintype "bidirectional"))
      (node (ref "R9") (pin "2") (pinfunction "2_2") (pintype "passive"))
    )
    (net (code "11") (name "DAC_2") (class "Default")
      (node (ref "IC17") (pin "3") (pinfunction "X_3") (pintype "bidirectional"))
      (node (ref "IC20") (pin "3") (pinfunction "X_3") (pintype "bidirectional"))
      (node (ref "R10") (pin "2") (pinfunction "2_2") (pintype "passive"))
    )
    (net (code "12") (name "DAC_3") (class "Default")
      (node (ref "IC14") (pin "3") (pinfunction "X_3") (pintype "bidirectional"))
      (node (ref "IC7") (pin "3") (pinfunction "X_3") (pintype "bidirectional"))
      (node (ref "R11") (pin "2") (pinfunction "2_2") (pintype "passive"))
    )
    (net (code "13") (name "DAC_4") (class "Default")
      (node (ref "IC1") (pin "3") (pinfunction "X_3") (pintype "bidirectional"))
      (node (ref "IC11") (pin "3") (pinfunction "X_3") (pintype "bidirectional"))
      (node (ref "R12") (pin "2") (pinfunction "2_2") (pintype "passive"))
    )
    (net (code "14") (name "DAC_RAW_1") (class "Default")
      (node (ref "IC2") (pin "1") (pinfunction "OUT_A_1") (pintype "bidirectional"))
      (node (ref "IC8") (pin "3") (pinfunction "+IN_3") (pintype "input"))
    )
    (net (code "15") (name "DAC_RAW_2") (class "Default")
      (node (ref "IC2") (pin "2") (pinfunction "OUT_B_2") (pintype "bidirectional"))
      (node (ref "IC8") (pin "5") (pinfunction "+IN_5") (pintype "input"))
    )
    (net (code "16") (name "DAC_RAW_3") (class "Default")
      (node (ref "IC2") (pin "7") (pinfunction "OUT_C_7") (pintype "bidirectional"))
      (node (ref "IC8") (pin "10") (pinfunction "+IN_10") (pintype "input"))
    )
    (net (code "17") (name "DAC_RAW_4") (class "Default")
      (node (ref "IC2") (pin "8") (pinfunction "OUT_D_8") (pintype "bidirectional"))
      (node (ref "IC8") (pin "12") (pinfunction "+IN_12") (pintype "input"))
    )
    (net (code "18") (name "INH_0") (class "Default")
      (node (ref "IC1") (pin "6") (pinfunction "INH_6") (pintype "input"))
      (node (ref "IC20") (pin "6") (pinfunction "INH_6") (pintype "input"))
      (node (ref "IC26") (pin "6") (pinfunction "INH_6") (pintype "input"))
      (node (ref "IC7") (pin "6") (pinfunction "INH_6") (pintype "input"))
      (node (ref "X6") (pin "3") (pinfunction "3_3") (pintype "passive"))
    )
    (net (code "19") (name "INH_1") (class "Default")
      (node (ref "IC11") (pin "6") (pinfunction "INH_6") (pintype "input"))
      (node (ref "IC14") (pin "6") (pinfunction "INH_6") (pintype "input"))
      (node (ref "IC17") (pin "6") (pinfunction "INH_6") (pintype "input"))
      (node (ref "X6") (pin "6") (pinfunction "6_6") (pintype "passive"))
    )
    (net (code "20") (name "IN_0") (class "Default")
      (node (ref "C13") (pin "2") (pinfunction "2_2") (pintype "passive"))
      (node (ref "IC1") (pin "13") (pinfunction "X0_13") (pintype "bidirectional"))
      (node (ref "IC3") (pin "12") (pinfunction "+IN_12") (pintype "input"))
    )
    (net (code "21") (name "IN_1") (class "Default")
      (node (ref "C12") (pin "2") (pinfunction "2_2") (pintype "passive"))
      (node (ref "IC1") (pin "14") (pinfunction "X1_14") (pintype "bidirectional"))
      (node (ref "IC3") (pin "10") (pinfunction "+IN_10") (pintype "input"))
    )
    (net (code "22") (name "IN_2") (class "Default")
      (node (ref "C11") (pin "2") (pinfunction "2_2") (pintype "passive"))
      (node (ref "IC1") (pin "15") (pinfunction "X2_15") (pintype "bidirectional"))
      (node (ref "IC3") (pin "5") (pinfunction "+IN_5") (pintype "input"))
    )
    (net (code "23") (name "IN_3") (class "Default")
      (node (ref "C7") (pin "2") (pinfunction "2_2") (pintype "passive"))
      (node (ref "IC1") (pin "12") (pinfunction "X3_12") (pintype "bidirectional"))
      (node (ref "IC3") (pin "3") (pinfunction "+IN_3") (pintype "input"))
    )
    (net (code "24") (name "IN_4") (class "Default")
      (node (ref "C25") (pin "2") (pinfunction "2_2") (pintype "passive"))
      (node (ref "IC1") (pin "1") (pinfunction "X4_1") (pintype "bidirectional"))
      (node (ref "IC6") (pin "12") (pinfunction "+IN_12") (pintype "input"))
    )
    (net (code "25") (name "IN_5") (class "Default")
      (node (ref "C18") (pin "2") (pinfunction "2_2") (pintype "passive"))
      (node (ref "IC1") (pin "5") (pinfunction "X5_5") (pintype "bidirectional"))
      (node (ref "IC6") (pin "10") (pinfunction "+IN_10") (pintype "input"))
    )
    (net (code "26") (name "IN_6") (class "Default")
      (node (ref "C17") (pin "2") (pinfunction "2_2") (pintype "passive"))
      (node (ref "IC1") (pin "2") (pinfunction "X6_2") (pintype "bidirectional"))
      (node (ref "IC6") (pin "5") (pinfunction "+IN_5") (pintype "input"))
    )
    (net (code "27") (name "IN_7") (class "Default")
      (node (ref "C16") (pin "2") (pinfunction "2_2") (pintype "passive"))
      (node (ref "IC1") (pin "4") (pinfunction "X7_4") (pintype "bidirectional"))
      (node (ref "IC6") (pin "3") (pinfunction "+IN_3") (pintype "input"))
    )
    (net (code "28") (name "IN_8") (class "Default")
      (node (ref "C46") (pin "2") (pinfunction "2_2") (pintype "passive"))
      (node (ref "IC11") (pin "13") (pinfunction "X0_13") (pintype "bidirectional"))
      (node (ref "IC12") (pin "12") (pinfunction "+IN_12") (pintype "input"))
    )
    (net (code "29") (name "IN_9") (class "Default")
      (node (ref "C45") (pin "2") (pinfunction "2_2") (pintype "passive"))
      (node (ref "IC11") (pin "14") (pinfunction "X1_14") (pintype "bidirectional"))
      (node (ref "IC12") (pin "10") (pinfunction "+IN_10") (pintype "input"))
    )
    (net (code "30") (name "IN_10") (class "Default")
      (node (ref "C44") (pin "2") (pinfunction "2_2") (pintype "passive"))
      (node (ref "IC11") (pin "15") (pinfunction "X2_15") (pintype "bidirectional"))
      (node (ref "IC12") (pin "5") (pinfunction "+IN_5") (pintype "input"))
    )
    (net (code "31") (name "IN_11") (class "Default")
      (node (ref "C43") (pin "2") (pinfunction "2_2") (pintype "passive"))
      (node (ref "IC11") (pin "12") (pinfunction "X3_12") (pintype "bidirectional"))
      (node (ref "IC12") (pin "3") (pinfunction "+IN_3") (pintype "input"))
    )
    (net (code "32") (name "IN_12") (class "Default")
      (node (ref "C52") (pin "2") (pinfunction "2_2") (pintype "passive"))
      (node (ref "IC11") (pin "1") (pinfunction "X4_1") (pintype "bidirectional"))
      (node (ref "IC13") (pin "12") (pinfunction "+IN_12") (pintype "input"))
    )
    (net (code "33") (name "IN_13") (class "Default")
      (node (ref "C51") (pin "2") (pinfunction "2_2") (pintype "passive"))
      (node (ref "IC11") (pin "5") (pinfunction "X5_5") (pintype "bidirectional"))
      (node (ref "IC13") (pin "10") (pinfunction "+IN_10") (pintype "input"))
    )
    (net (code "34") (name "IN_14") (class "Default")
      (node (ref "C50") (pin "2") (pinfunction "2_2") (pintype "passive"))
      (node (ref "IC11") (pin "2") (pinfunction "X6_2") (pintype "bidirectional"))
      (node (ref "IC13") (pin "5") (pinfunction "+IN_5") (pintype "input"))
    )
    (net (code "35") (name "IN_15") (class "Default")
      (node (ref "C49") (pin "2") (pinfunction "2_2") (pintype "passive"))
      (node (ref "IC11") (pin "4") (pinfunction "X7_4") (pintype "bidirectional"))
      (node (ref "IC13") (pin "3") (pinfunction "+IN_3") (pintype "input"))
    )
    (net (code "36") (name "IN_16") (class "Default")
      (node (ref "C32") (pin "2") (pinfunction "2_2") (pintype "passive"))
      (node (ref "IC7") (pin "13") (pinfunction "X0_13") (pintype "bidirectional"))
      (node (ref "IC9") (pin "12") (pinfunction "+IN_12") (pintype "input"))
    )
    (net (code "37") (name "IN_17") (class "Default")
      (node (ref "C31") (pin "2") (pinfunction "2_2") (pintype "passive"))
      (node (ref "IC7") (pin "14") (pinfunction "X1_14") (pintype "bidirectional"))
      (node (ref "IC9") (pin "10") (pinfunction "+IN_10") (pintype "input"))
    )
    (net (code "38") (name "IN_18") (class "Default")
      (node (ref "C30") (pin "2") (pinfunction "2_2") (pintype "passive"))
      (node (ref "IC7") (pin "15") (pinfunction "X2_15") (pintype "bidirectional"))
      (node (ref "IC9") (pin "5") (pinfunction "+IN_5") (pintype "input"))
    )
    (net (code "39") (name "IN_19") (class "Default")
      (node (ref "C29") (pin "2") (pinfunction "2_2") (pintype "passive"))
      (node (ref "IC7") (pin "12") (pinfunction "X3_12") (pintype "bidirectional"))
      (node (ref "IC9") (pin "3") (pinfunction "+IN_3") (pintype "input"))
    )
    (net (code "40") (name "IN_20") (class "Default")
      (node (ref "C38") (pin "2") (pinfunction "2_2") (pintype "passive"))
      (node (ref "IC10") (pin "12") (pinfunction "+IN_12") (pintype "input"))
      (node (ref "IC7") (pin "1") (pinfunction "X4_1") (pintype "bidirectional"))
    )
    (net (code "41") (name "IN_21") (class "Default")
      (node (ref "C37") (pin "2") (pinfunction "2_2") (pintype "passive"))
      (node (ref "IC10") (pin "10") (pinfunction "+IN_10") (pintype "input"))
      (node (ref "IC7") (pin "5") (pinfunction "X5_5") (pintype "bidirectional"))
    )
    (net (code "42") (name "IN_22") (class "Default")
      (node (ref "C36") (pin "2") (pinfunction "2_2") (pintype "passive"))
      (node (ref "IC10") (pin "5") (pinfunction "+IN_5") (pintype "input"))
      (node (ref "IC7") (pin "2") (pinfunction "X6_2") (pintype "bidirectional"))
    )
    (net (code "43") (name "IN_23") (class "Default")
      (node (ref "C35") (pin "2") (pinfunction "2_2") (pintype "passive"))
      (node (ref "IC10") (pin "3") (pinfunction "+IN_3") (pintype "input"))
      (node (ref "IC7") (pin "4") (pinfunction "X7_4") (pintype "bidirectional"))
    )
    (net (code "44") (name "IN_24") (class "Default")
      (node (ref "C59") (pin "2") (pinfunction "2_2") (pintype "passive"))
      (node (ref "IC14") (pin "13") (pinfunction "X0_13") (pintype "bidirectional"))
      (node (ref "IC15") (pin "12") (pinfunction "+IN_12") (pintype "input"))
    )
    (net (code "45") (name "IN_25") (class "Default")
      (node (ref "C58") (pin "2") (pinfunction "2_2") (pintype "passive"))
      (node (ref "IC14") (pin "14") (pinfunction "X1_14") (pintype "bidirectional"))
      (node (ref "IC15") (pin "10") (pinfunction "+IN_10") (pintype "input"))
    )
    (net (code "46") (name "IN_26") (class "Default")
      (node (ref "C57") (pin "2") (pinfunction "2_2") (pintype "passive"))
      (node (ref "IC14") (pin "15") (pinfunction "X2_15") (pintype "bidirectional"))
      (node (ref "IC15") (pin "5") (pinfunction "+IN_5") (pintype "input"))
    )
    (net (code "47") (name "IN_27") (class "Default")
      (node (ref "C56") (pin "2") (pinfunction "2_2") (pintype "passive"))
      (node (ref "IC14") (pin "12") (pinfunction "X3_12") (pintype "bidirectional"))
      (node (ref "IC15") (pin "3") (pinfunction "+IN_3") (pintype "input"))
    )
    (net (code "48") (name "IN_28") (class "Default")
      (node (ref "C65") (pin "2") (pinfunction "2_2") (pintype "passive"))
      (node (ref "IC14") (pin "1") (pinfunction "X4_1") (pintype "bidirectional"))
      (node (ref "IC16") (pin "12") (pinfunction "+IN_12") (pintype "input"))
    )
    (net (code "49") (name "IN_29") (class "Default")
      (node (ref "C64") (pin "2") (pinfunction "2_2") (pintype "passive"))
      (node (ref "IC14") (pin "5") (pinfunction "X5_5") (pintype "bidirectional"))
      (node (ref "IC16") (pin "10") (pinfunction "+IN_10") (pintype "input"))
    )
    (net (code "50") (name "IN_30") (class "Default")
      (node (ref "C63") (pin "2") (pinfunction "2_2") (pintype "passive"))
      (node (ref "IC14") (pin "2") (pinfunction "X6_2") (pintype "bidirectional"))
      (node (ref "IC16") (pin "5") (pinfunction "+IN_5") (pintype "input"))
    )
    (net (code "51") (name "IN_31") (class "Default")
      (node (ref "C62") (pin "2") (pinfunction "2_2") (pintype "passive"))
      (node (ref "IC14") (pin "4") (pinfunction "X7_4") (pintype "bidirectional"))
      (node (ref "IC16") (pin "3") (pinfunction "+IN_3") (pintype "input"))
    )
    (net (code "52") (name "IN_32") (class "Default")
      (node (ref "C85") (pin "2") (pinfunction "2_2") (pintype "passive"))
      (node (ref "IC20") (pin "13") (pinfunction "X0_13") (pintype "bidirectional"))
      (node (ref "IC21") (pin "12") (pinfunction "+IN_12") (pintype "input"))
    )
    (net (code "53") (name "IN_33") (class "Default")
      (node (ref "C84") (pin "2") (pinfunction "2_2") (pintype "passive"))
      (node (ref "IC20") (pin "14") (pinfunction "X1_14") (pintype "bidirectional"))
      (node (ref "IC21") (pin "10") (pinfunction "+IN_10") (pintype "input"))
    )
    (net (code "54") (name "IN_34") (class "Default")
      (node (ref "C83") (pin "2") (pinfunction "2_2") (pintype "passive"))
      (node (ref "IC20") (pin "15") (pinfunction "X2_15") (pintype "bidirectional"))
      (node (ref "IC21") (pin "5") (pinfunction "+IN_5") (pintype "input"))
    )
    (net (code "55") (name "IN_35") (class "Default")
      (node (ref "C82") (pin "2") (pinfunction "2_2") (pintype "passive"))
      (node (ref "IC20") (pin "12") (pinfunction "X3_12") (pintype "bidirectional"))
      (node (ref "IC21") (pin "3") (pinfunction "+IN_3") (pintype "input"))
    )
    (net (code "56") (name "IN_36") (class "Default")
      (node (ref "C91") (pin "2") (pinfunction "2_2") (pintype "passive"))
      (node (ref "IC20") (pin "1") (pinfunction "X4_1") (pintype "bidirectional"))
      (node (ref "IC22") (pin "12") (pinfunction "+IN_12") (pintype "input"))
    )
    (net (code "57") (name "IN_37") (class "Default")
      (node (ref "C90") (pin "2") (pinfunction "2_2") (pintype "passive"))
      (node (ref "IC20") (pin "5") (pinfunction "X5_5") (pintype "bidirectional"))
      (node (ref "IC22") (pin "10") (pinfunction "+IN_10") (pintype "input"))
    )
    (net (code "58") (name "IN_38") (class "Default")
      (node (ref "C89") (pin "2") (pinfunction "2_2") (pintype "passive"))
      (node (ref "IC20") (pin "2") (pinfunction "X6_2") (pintype "bidirectional"))
      (node (ref "IC22") (pin "5") (pinfunction "+IN_5") (pintype "input"))
    )
    (net (code "59") (name "IN_39") (class "Default")
      (node (ref "C88") (pin "2") (pinfunction "2_2") (pintype "passive"))
      (node (ref "IC20") (pin "4") (pinfunction "X7_4") (pintype "bidirectional"))
      (node (ref "IC22") (pin "3") (pinfunction "+IN_3") (pintype "input"))
    )
    (net (code "60") (name "IN_40") (class "Default")
      (node (ref "C72") (pin "2") (pinfunction "2_2") (pintype "passive"))
      (node (ref "IC17") (pin "13") (pinfunction "X0_13") (pintype "bidirectional"))
      (node (ref "IC18") (pin "12") (pinfunction "+IN_12") (pintype "input"))
    )
    (net (code "61") (name "IN_41") (class "Default")
      (node (ref "C71") (pin "2") (pinfunction "2_2") (pintype "passive"))
      (node (ref "IC17") (pin "14") (pinfunction "X1_14") (pintype "bidirectional"))
      (node (ref "IC18") (pin "10") (pinfunction "+IN_10") (pintype "input"))
    )
    (net (code "62") (name "IN_42") (class "Default")
      (node (ref "C70") (pin "2") (pinfunction "2_2") (pintype "passive"))
      (node (ref "IC17") (pin "15") (pinfunction "X2_15") (pintype "bidirectional"))
      (node (ref "IC18") (pin "5") (pinfunction "+IN_5") (pintype "input"))
    )
    (net (code "63") (name "IN_43") (class "Default")
      (node (ref "C69") (pin "2") (pinfunction "2_2") (pintype "passive"))
      (node (ref "IC17") (pin "12") (pinfunction "X3_12") (pintype "bidirectional"))
      (node (ref "IC18") (pin "3") (pinfunction "+IN_3") (pintype "input"))
    )
    (net (code "64") (name "IN_44") (class "Default")
      (node (ref "C78") (pin "2") (pinfunction "2_2") (pintype "passive"))
      (node (ref "IC17") (pin "1") (pinfunction "X4_1") (pintype "bidirectional"))
      (node (ref "IC19") (pin "12") (pinfunction "+IN_12") (pintype "input"))
    )
    (net (code "65") (name "IN_45") (class "Default")
      (node (ref "C77") (pin "2") (pinfunction "2_2") (pintype "passive"))
      (node (ref "IC17") (pin "5") (pinfunction "X5_5") (pintype "bidirectional"))
      (node (ref "IC19") (pin "10") (pinfunction "+IN_10") (pintype "input"))
    )
    (net (code "66") (name "IN_46") (class "Default")
      (node (ref "C76") (pin "2") (pinfunction "2_2") (pintype "passive"))
      (node (ref "IC17") (pin "2") (pinfunction "X6_2") (pintype "bidirectional"))
      (node (ref "IC19") (pin "5") (pinfunction "+IN_5") (pintype "input"))
    )
    (net (code "67") (name "IN_47") (class "Default")
      (node (ref "C75") (pin "2") (pinfunction "2_2") (pintype "passive"))
      (node (ref "IC17") (pin "4") (pinfunction "X7_4") (pintype "bidirectional"))
      (node (ref "IC19") (pin "3") (pinfunction "+IN_3") (pintype "input"))
    )
    (net (code "68") (name "IN_48") (class "Default")
      (node (ref "C111") (pin "2") (pinfunction "2_2") (pintype "passive"))
      (node (ref "IC26") (pin "13") (pinfunction "X0_13") (pintype "bidirectional"))
      (node (ref "IC27") (pin "12") (pinfunction "+IN_12") (pintype "input"))
    )
    (net (code "69") (name "IN_49") (class "Default")
      (node (ref "C110") (pin "2") (pinfunction "2_2") (pintype "passive"))
      (node (ref "IC26") (pin "14") (pinfunction "X1_14") (pintype "bidirectional"))
      (node (ref "IC27") (pin "10") (pinfunction "+IN_10") (pintype "input"))
    )
    (net (code "70") (name "IN_50") (class "Default")
      (node (ref "C109") (pin "2") (pinfunction "2_2") (pintype "passive"))
      (node (ref "IC26") (pin "15") (pinfunction "X2_15") (pintype "bidirectional"))
      (node (ref "IC27") (pin "5") (pinfunction "+IN_5") (pintype "input"))
    )
    (net (code "71") (name "IN_51") (class "Default")
      (node (ref "C108") (pin "2") (pinfunction "2_2") (pintype "passive"))
      (node (ref "IC26") (pin "12") (pinfunction "X3_12") (pintype "bidirectional"))
      (node (ref "IC27") (pin "3") (pinfunction "+IN_3") (pintype "input"))
    )
    (net (code "72") (name "IN_52") (class "Default")
      (node (ref "C117") (pin "2") (pinfunction "2_2") (pintype "passive"))
      (node (ref "IC26") (pin "1") (pinfunction "X4_1") (pintype "bidirectional"))
      (node (ref "IC28") (pin "12") (pinfunction "+IN_12") (pintype "input"))
    )
    (net (code "73") (name "IN_53") (class "Default")
      (node (ref "C116") (pin "2") (pinfunction "2_2") (pintype "passive"))
      (node (ref "IC26") (pin "5") (pinfunction "X5_5") (pintype "bidirectional"))
      (node (ref "IC28") (pin "10") (pinfunction "+IN_10") (pintype "input"))
    )
    (net (code "74") (name "IN_54") (class "Default")
      (node (ref "C115") (pin "2") (pinfunction "2_2") (pintype "passive"))
      (node (ref "IC26") (pin "2") (pinfunction "X6_2") (pintype "bidirectional"))
      (node (ref "IC28") (pin "5") (pinfunction "+IN_5") (pintype "input"))
    )
    (net (code "75") (name "IN_55") (class "Default")
      (node (ref "C114") (pin "2") (pinfunction "2_2") (pintype "passive"))
      (node (ref "IC26") (pin "4") (pinfunction "X7_4") (pintype "bidirectional"))
      (node (ref "IC28") (pin "3") (pinfunction "+IN_3") (pintype "input"))
    )
    (net (code "76") (name "LDAC") (class "Default")
      (node (ref "IC2") (pin "16") (pinfunction "LDAC_16") (pintype "bidirectional"))
      (node (ref "X6") (pin "9") (pinfunction "9_9") (pintype "passive"))
    )
    (net (code "77") (name "Net-(IC2-IOVDD)") (class "Default")
      (node (ref "C9") (pin "1") (pinfunction "1_1") (pintype "passive"))
      (node (ref "IC2") (pin "12") (pinfunction "IOVDD_12") (pintype "power_in"))
      (node (ref "JP1") (pin "2") (pinfunction "2_2") (pintype "passive"))
    )
    (net (code "78") (name "Net-(IC8A--IN)") (class "Default")
      (node (ref "IC8") (pin "2") (pinfunction "-IN_2") (pintype "input"))
      (node (ref "R1") (pin "1") (pinfunction "1_1") (pintype "passive"))
      (node (ref "R2") (pin "2") (pinfunction "2_2") (pintype "passive"))
    )
    (net (code "79") (name "Net-(IC8A-OUT)") (class "Default")
      (node (ref "IC8") (pin "1") (pinfunction "OUT_1") (pintype "output"))
      (node (ref "R1") (pin "2") (pinfunction "2_2") (pintype "passive"))
      (node (ref "R9") (pin "1") (pinfunction "1_1") (pintype "passive"))
    )
    (net (code "80") (name "Net-(IC8B--IN)") (class "Default")
      (node (ref "IC8") (pin "6") (pinfunction "-IN_6") (pintype "input"))
      (node (ref "R3") (pin "2") (pinfunction "2_2") (pintype "passive"))
      (node (ref "R4") (pin "1") (pinfunction "1_1") (pintype "passive"))
    )
    (net (code "81") (name "Net-(IC8B-OUT)") (class "Default")
      (node (ref "IC8") (pin "7") (pinfunction "OUT_7") (pintype "output"))
      (node (ref "R10") (pin "1") (pinfunction "1_1") (pintype "passive"))
      (node (ref "R4") (pin "2") (pinfunction "2_2") (pintype "passive"))
    )
    (net (code "82") (name "Net-(IC8C--IN)") (class "Default")
      (node (ref "IC8") (pin "9") (pinfunction "-IN_9") (pintype "input"))
      (node (ref "R5") (pin "2") (pinfunction "2_2") (pintype "passive"))
      (node (ref "R6") (pin "1") (pinfunction "1_1") (pintype "passive"))
    )
    (net (code "83") (name "Net-(IC8C-OUT)") (class "Default")
      (node (ref "IC8") (pin "8") (pinfunction "OUT_8") (pintype "output"))
      (node (ref "R11") (pin "1") (pinfunction "1_1") (pintype "passive"))
      (node (ref "R6") (pin "2") (pinfunction "2_2") (pintype "passive"))
    )
    (net (code "84") (name "Net-(IC8D--IN)") (class "Default")
      (node (ref "IC8") (pin "13") (pinfunction "-IN_13") (pintype "input"))
      (node (ref "R7") (pin "2") (pinfunction "2_2") (pintype "passive"))
      (node (ref "R8") (pin "1") (pinfunction "1_1") (pintype "passive"))
    )
    (net (code "85") (name "Net-(IC8D-OUT)") (class "Default")
      (node (ref "IC8") (pin "14") (pinfunction "OUT_14") (pintype "output"))
      (node (ref "R12") (pin "1") (pinfunction "1_1") (pintype "passive"))
      (node (ref "R8") (pin "2") (pinfunction "2_2") (pintype "passive"))
    )
    (net (code "86") (name "OUT_0") (class "Default")
      (node (ref "IC3") (pin "13") (pinfunction "-IN_13") (pintype "input"))
      (node (ref "IC3") (pin "14") (pinfunction "OUT_14") (pintype "output"))
      (node (ref "U$2") (pin "1") (pinfunction "1_1") (pintype "passive"))
    )
    (net (code "87") (name "OUT_1") (class "Default")
      (node (ref "IC3") (pin "8") (pinfunction "OUT_8") (pintype "output"))
      (node (ref "IC3") (pin "9") (pinfunction "-IN_9") (pintype "input"))
      (node (ref "U$2") (pin "3") (pinfunction "3_3") (pintype "passive"))
    )
    (net (code "88") (name "OUT_2") (class "Default")
      (node (ref "IC3") (pin "6") (pinfunction "-IN_6") (pintype "input"))
      (node (ref "IC3") (pin "7") (pinfunction "OUT_7") (pintype "output"))
      (node (ref "U$2") (pin "5") (pinfunction "5_5") (pintype "passive"))
    )
    (net (code "89") (name "OUT_3") (class "Default")
      (node (ref "IC3") (pin "1") (pinfunction "OUT_1") (pintype "output"))
      (node (ref "IC3") (pin "2") (pinfunction "-IN_2") (pintype "input"))
      (node (ref "U$2") (pin "7") (pinfunction "7_7") (pintype "passive"))
    )
    (net (code "90") (name "OUT_4") (class "Default")
      (node (ref "IC6") (pin "13") (pinfunction "-IN_13") (pintype "input"))
      (node (ref "IC6") (pin "14") (pinfunction "OUT_14") (pintype "output"))
      (node (ref "U$2") (pin "9") (pinfunction "9_9") (pintype "passive"))
    )
    (net (code "91") (name "OUT_5") (class "Default")
      (node (ref "IC6") (pin "8") (pinfunction "OUT_8") (pintype "output"))
      (node (ref "IC6") (pin "9") (pinfunction "-IN_9") (pintype "input"))
      (node (ref "U$2") (pin "11") (pinfunction "11_11") (pintype "passive"))
    )
    (net (code "92") (name "OUT_6") (class "Default")
      (node (ref "IC6") (pin "6") (pinfunction "-IN_6") (pintype "input"))
      (node (ref "IC6") (pin "7") (pinfunction "OUT_7") (pintype "output"))
      (node (ref "U$2") (pin "13") (pinfunction "13_13") (pintype "passive"))
    )
    (net (code "93") (name "OUT_7") (class "Default")
      (node (ref "IC6") (pin "1") (pinfunction "OUT_1") (pintype "output"))
      (node (ref "IC6") (pin "2") (pinfunction "-IN_2") (pintype "input"))
      (node (ref "U$2") (pin "15") (pinfunction "15_15") (pintype "passive"))
    )
    (net (code "94") (name "OUT_8") (class "Default")
      (node (ref "IC12") (pin "13") (pinfunction "-IN_13") (pintype "input"))
      (node (ref "IC12") (pin "14") (pinfunction "OUT_14") (pintype "output"))
      (node (ref "U$2") (pin "17") (pinfunction "17_17") (pintype "passive"))
    )
    (net (code "95") (name "OUT_9") (class "Default")
      (node (ref "IC12") (pin "8") (pinfunction "OUT_8") (pintype "output"))
      (node (ref "IC12") (pin "9") (pinfunction "-IN_9") (pintype "input"))
      (node (ref "U$2") (pin "19") (pinfunction "19_19") (pintype "passive"))
    )
    (net (code "96") (name "OUT_10") (class "Default")
      (node (ref "IC12") (pin "6") (pinfunction "-IN_6") (pintype "input"))
      (node (ref "IC12") (pin "7") (pinfunction "OUT_7") (pintype "output"))
      (node (ref "U$2") (pin "21") (pinfunction "21_21") (pintype "passive"))
    )
    (net (code "97") (name "OUT_11") (class "Default")
      (node (ref "IC12") (pin "1") (pinfunction "OUT_1") (pintype "output"))
      (node (ref "IC12") (pin "2") (pinfunction "-IN_2") (pintype "input"))
      (node (ref "U$2") (pin "23") (pinfunction "23_23") (pintype "passive"))
    )
    (net (code "98") (name "OUT_12") (class "Default")
      (node (ref "IC13") (pin "13") (pinfunction "-IN_13") (pintype "input"))
      (node (ref "IC13") (pin "14") (pinfunction "OUT_14") (pintype "output"))
      (node (ref "U$2") (pin "25") (pinfunction "25_25") (pintype "passive"))
    )
    (net (code "99") (name "OUT_13") (class "Default")
      (node (ref "IC13") (pin "8") (pinfunction "OUT_8") (pintype "output"))
      (node (ref "IC13") (pin "9") (pinfunction "-IN_9") (pintype "input"))
      (node (ref "U$2") (pin "27") (pinfunction "27_27") (pintype "passive"))
    )
    (net (code "100") (name "OUT_14") (class "Default")
      (node (ref "IC13") (pin "6") (pinfunction "-IN_6") (pintype "input"))
      (node (ref "IC13") (pin "7") (pinfunction "OUT_7") (pintype "output"))
      (node (ref "U$2") (pin "29") (pinfunction "29_29") (pintype "passive"))
    )
    (net (code "101") (name "OUT_15") (class "Default")
      (node (ref "IC13") (pin "1") (pinfunction "OUT_1") (pintype "output"))
      (node (ref "IC13") (pin "2") (pinfunction "-IN_2") (pintype "input"))
      (node (ref "X5") (pin "1") (pinfunction "1_1") (pintype "passive"))
    )
    (net (code "102") (name "OUT_16") (class "Default")
      (node (ref "IC9") (pin "13") (pinfunction "-IN_13") (pintype "input"))
      (node (ref "IC9") (pin "14") (pinfunction "OUT_14") (pintype "output"))
      (node (ref "U$3") (pin "1") (pinfunction "1_1") (pintype "passive"))
    )
    (net (code "103") (name "OUT_17") (class "Default")
      (node (ref "IC9") (pin "8") (pinfunction "OUT_8") (pintype "output"))
      (node (ref "IC9") (pin "9") (pinfunction "-IN_9") (pintype "input"))
      (node (ref "U$3") (pin "3") (pinfunction "3_3") (pintype "passive"))
    )
    (net (code "104") (name "OUT_18") (class "Default")
      (node (ref "IC9") (pin "6") (pinfunction "-IN_6") (pintype "input"))
      (node (ref "IC9") (pin "7") (pinfunction "OUT_7") (pintype "output"))
      (node (ref "U$3") (pin "5") (pinfunction "5_5") (pintype "passive"))
    )
    (net (code "105") (name "OUT_19") (class "Default")
      (node (ref "IC9") (pin "1") (pinfunction "OUT_1") (pintype "output"))
      (node (ref "IC9") (pin "2") (pinfunction "-IN_2") (pintype "input"))
      (node (ref "U$3") (pin "7") (pinfunction "7_7") (pintype "passive"))
    )
    (net (code "106") (name "OUT_20") (class "Default")
      (node (ref "IC10") (pin "13") (pinfunction "-IN_13") (pintype "input"))
      (node (ref "IC10") (pin "14") (pinfunction "OUT_14") (pintype "output"))
      (node (ref "U$3") (pin "9") (pinfunction "9_9") (pintype "passive"))
    )
    (net (code "107") (name "OUT_21") (class "Default")
      (node (ref "IC10") (pin "8") (pinfunction "OUT_8") (pintype "output"))
      (node (ref "IC10") (pin "9") (pinfunction "-IN_9") (pintype "input"))
      (node (ref "U$3") (pin "11") (pinfunction "11_11") (pintype "passive"))
    )
    (net (code "108") (name "OUT_22") (class "Default")
      (node (ref "IC10") (pin "6") (pinfunction "-IN_6") (pintype "input"))
      (node (ref "IC10") (pin "7") (pinfunction "OUT_7") (pintype "output"))
      (node (ref "U$3") (pin "13") (pinfunction "13_13") (pintype "passive"))
    )
    (net (code "109") (name "OUT_23") (class "Default")
      (node (ref "IC10") (pin "1") (pinfunction "OUT_1") (pintype "output"))
      (node (ref "IC10") (pin "2") (pinfunction "-IN_2") (pintype "input"))
      (node (ref "U$3") (pin "15") (pinfunction "15_15") (pintype "passive"))
    )
    (net (code "110") (name "OUT_24") (class "Default")
      (node (ref "IC15") (pin "13") (pinfunction "-IN_13") (pintype "input"))
      (node (ref "IC15") (pin "14") (pinfunction "OUT_14") (pintype "output"))
      (node (ref "U$3") (pin "17") (pinfunction "17_17") (pintype "passive"))
    )
    (net (code "111") (name "OUT_25") (class "Default")
      (node (ref "IC15") (pin "8") (pinfunction "OUT_8") (pintype "output"))
      (node (ref "IC15") (pin "9") (pinfunction "-IN_9") (pintype "input"))
      (node (ref "U$3") (pin "19") (pinfunction "19_19") (pintype "passive"))
    )
    (net (code "112") (name "OUT_26") (class "Default")
      (node (ref "IC15") (pin "6") (pinfunction "-IN_6") (pintype "input"))
      (node (ref "IC15") (pin "7") (pinfunction "OUT_7") (pintype "output"))
      (node (ref "U$3") (pin "21") (pinfunction "21_21") (pintype "passive"))
    )
    (net (code "113") (name "OUT_27") (class "Default")
      (node (ref "IC15") (pin "1") (pinfunction "OUT_1") (pintype "output"))
      (node (ref "IC15") (pin "2") (pinfunction "-IN_2") (pintype "input"))
      (node (ref "U$3") (pin "23") (pinfunction "23_23") (pintype "passive"))
    )
    (net (code "114") (name "OUT_28") (class "Default")
      (node (ref "IC16") (pin "13") (pinfunction "-IN_13") (pintype "input"))
      (node (ref "IC16") (pin "14") (pinfunction "OUT_14") (pintype "output"))
      (node (ref "U$3") (pin "25") (pinfunction "25_25") (pintype "passive"))
    )
    (net (code "115") (name "OUT_29") (class "Default")
      (node (ref "IC16") (pin "8") (pinfunction "OUT_8") (pintype "output"))
      (node (ref "IC16") (pin "9") (pinfunction "-IN_9") (pintype "input"))
      (node (ref "U$3") (pin "27") (pinfunction "27_27") (pintype "passive"))
    )
    (net (code "116") (name "OUT_30") (class "Default")
      (node (ref "IC16") (pin "6") (pinfunction "-IN_6") (pintype "input"))
      (node (ref "IC16") (pin "7") (pinfunction "OUT_7") (pintype "output"))
      (node (ref "U$3") (pin "29") (pinfunction "29_29") (pintype "passive"))
    )
    (net (code "117") (name "OUT_31") (class "Default")
      (node (ref "IC16") (pin "1") (pinfunction "OUT_1") (pintype "output"))
      (node (ref "IC16") (pin "2") (pinfunction "-IN_2") (pintype "input"))
      (node (ref "X9") (pin "1") (pinfunction "1_1") (pintype "passive"))
    )
    (net (code "118") (name "OUT_32") (class "Default")
      (node (ref "IC21") (pin "13") (pinfunction "-IN_13") (pintype "input"))
      (node (ref "IC21") (pin "14") (pinfunction "OUT_14") (pintype "output"))
      (node (ref "X9") (pin "2") (pinfunction "2_2") (pintype "passive"))
    )
    (net (code "119") (name "OUT_33") (class "Default")
      (node (ref "IC21") (pin "8") (pinfunction "OUT_8") (pintype "output"))
      (node (ref "IC21") (pin "9") (pinfunction "-IN_9") (pintype "input"))
      (node (ref "X10") (pin "1") (pinfunction "1_1") (pintype "passive"))
    )
    (net (code "120") (name "OUT_34") (class "Default")
      (node (ref "IC21") (pin "6") (pinfunction "-IN_6") (pintype "input"))
      (node (ref "IC21") (pin "7") (pinfunction "OUT_7") (pintype "output"))
      (node (ref "X10") (pin "3") (pinfunction "3_3") (pintype "passive"))
    )
    (net (code "121") (name "OUT_35") (class "Default")
      (node (ref "IC21") (pin "1") (pinfunction "OUT_1") (pintype "output"))
      (node (ref "IC21") (pin "2") (pinfunction "-IN_2") (pintype "input"))
      (node (ref "X10") (pin "5") (pinfunction "5_5") (pintype "passive"))
    )
    (net (code "122") (name "OUT_36") (class "Default")
      (node (ref "IC22") (pin "13") (pinfunction "-IN_13") (pintype "input"))
      (node (ref "IC22") (pin "14") (pinfunction "OUT_14") (pintype "output"))
      (node (ref "X10") (pin "7") (pinfunction "7_7") (pintype "passive"))
    )
    (net (code "123") (name "OUT_37") (class "Default")
      (node (ref "IC22") (pin "8") (pinfunction "OUT_8") (pintype "output"))
      (node (ref "IC22") (pin "9") (pinfunction "-IN_9") (pintype "input"))
      (node (ref "X10") (pin "9") (pinfunction "9_9") (pintype "passive"))
    )
    (net (code "124") (name "OUT_38") (class "Default")
      (node (ref "IC22") (pin "6") (pinfunction "-IN_6") (pintype "input"))
      (node (ref "IC22") (pin "7") (pinfunction "OUT_7") (pintype "output"))
      (node (ref "X10") (pin "11") (pinfunction "11_11") (pintype "passive"))
    )
    (net (code "125") (name "OUT_39") (class "Default")
      (node (ref "IC22") (pin "1") (pinfunction "OUT_1") (pintype "output"))
      (node (ref "IC22") (pin "2") (pinfunction "-IN_2") (pintype "input"))
      (node (ref "X10") (pin "13") (pinfunction "13_13") (pintype "passive"))
    )
    (net (code "126") (name "OUT_40") (class "Default")
      (node (ref "IC18") (pin "13") (pinfunction "-IN_13") (pintype "input"))
      (node (ref "IC18") (pin "14") (pinfunction "OUT_14") (pintype "output"))
      (node (ref "X4") (pin "1") (pinfunction "1_1") (pintype "passive"))
    )
    (net (code "127") (name "OUT_41") (class "Default")
      (node (ref "IC18") (pin "8") (pinfunction "OUT_8") (pintype "output"))
      (node (ref "IC18") (pin "9") (pinfunction "-IN_9") (pintype "input"))
      (node (ref "U$4") (pin "1") (pinfunction "1_1") (pintype "passive"))
    )
    (net (code "128") (name "OUT_42") (class "Default")
      (node (ref "IC18") (pin "6") (pinfunction "-IN_6") (pintype "input"))
      (node (ref "IC18") (pin "7") (pinfunction "OUT_7") (pintype "output"))
      (node (ref "U$4") (pin "3") (pinfunction "3_3") (pintype "passive"))
    )
    (net (code "129") (name "OUT_43") (class "Default")
      (node (ref "IC18") (pin "1") (pinfunction "OUT_1") (pintype "output"))
      (node (ref "IC18") (pin "2") (pinfunction "-IN_2") (pintype "input"))
      (node (ref "U$4") (pin "5") (pinfunction "5_5") (pintype "passive"))
    )
    (net (code "130") (name "OUT_44") (class "Default")
      (node (ref "IC19") (pin "13") (pinfunction "-IN_13") (pintype "input"))
      (node (ref "IC19") (pin "14") (pinfunction "OUT_14") (pintype "output"))
      (node (ref "U$4") (pin "7") (pinfunction "7_7") (pintype "passive"))
    )
    (net (code "131") (name "OUT_45") (class "Default")
      (node (ref "IC19") (pin "8") (pinfunction "OUT_8") (pintype "output"))
      (node (ref "IC19") (pin "9") (pinfunction "-IN_9") (pintype "input"))
      (node (ref "U$4") (pin "9") (pinfunction "9_9") (pintype "passive"))
    )
    (net (code "132") (name "OUT_46") (class "Default")
      (node (ref "IC19") (pin "6") (pinfunction "-IN_6") (pintype "input"))
      (node (ref "IC19") (pin "7") (pinfunction "OUT_7") (pintype "output"))
      (node (ref "U$4") (pin "11") (pinfunction "11_11") (pintype "passive"))
    )
    (net (code "133") (name "OUT_47") (class "Default")
      (node (ref "IC19") (pin "1") (pinfunction "OUT_1") (pintype "output"))
      (node (ref "IC19") (pin "2") (pinfunction "-IN_2") (pintype "input"))
      (node (ref "U$4") (pin "13") (pinfunction "13_13") (pintype "passive"))
    )
    (net (code "134") (name "OUT_48") (class "Default")
      (node (ref "IC27") (pin "13") (pinfunction "-IN_13") (pintype "input"))
      (node (ref "IC27") (pin "14") (pinfunction "OUT_14") (pintype "output"))
      (node (ref "U$4") (pin "15") (pinfunction "15_15") (pintype "passive"))
    )
    (net (code "135") (name "OUT_49") (class "Default")
      (node (ref "IC27") (pin "8") (pinfunction "OUT_8") (pintype "output"))
      (node (ref "IC27") (pin "9") (pinfunction "-IN_9") (pintype "input"))
      (node (ref "U$4") (pin "17") (pinfunction "17_17") (pintype "passive"))
    )
    (net (code "136") (name "OUT_50") (class "Default")
      (node (ref "IC27") (pin "6") (pinfunction "-IN_6") (pintype "input"))
      (node (ref "IC27") (pin "7") (pinfunction "OUT_7") (pintype "output"))
      (node (ref "U$4") (pin "19") (pinfunction "19_19") (pintype "passive"))
    )
    (net (code "137") (name "OUT_51") (class "Default")
      (node (ref "IC27") (pin "1") (pinfunction "OUT_1") (pintype "output"))
      (node (ref "IC27") (pin "2") (pinfunction "-IN_2") (pintype "input"))
      (node (ref "U$4") (pin "21") (pinfunction "21_21") (pintype "passive"))
    )
    (net (code "138") (name "OUT_52") (class "Default")
      (node (ref "IC28") (pin "13") (pinfunction "-IN_13") (pintype "input"))
      (node (ref "IC28") (pin "14") (pinfunction "OUT_14") (pintype "output"))
      (node (ref "U$4") (pin "23") (pinfunction "23_23") (pintype "passive"))
    )
    (net (code "139") (name "OUT_53") (class "Default")
      (node (ref "IC28") (pin "8") (pinfunction "OUT_8") (pintype "output"))
      (node (ref "IC28") (pin "9") (pinfunction "-IN_9") (pintype "input"))
      (node (ref "U$4") (pin "25") (pinfunction "25_25") (pintype "passive"))
    )
    (net (code "140") (name "OUT_54") (class "Default")
      (node (ref "IC28") (pin "6") (pinfunction "-IN_6") (pintype "input"))
      (node (ref "IC28") (pin "7") (pinfunction "OUT_7") (pintype "output"))
      (node (ref "U$4") (pin "27") (pinfunction "27_27") (pintype "passive"))
    )
    (net (code "141") (name "OUT_55") (class "Default")
      (node (ref "IC28") (pin "1") (pinfunction "OUT_1") (pintype "output"))
      (node (ref "IC28") (pin "2") (pinfunction "-IN_2") (pintype "input"))
      (node (ref "U$4") (pin "29") (pinfunction "29_29") (pintype "passive"))
    )
    (net (code "142") (name "SCK") (class "Default")
      (node (ref "IC2") (pin "10") (pinfunction "SCLK_10") (pintype "bidirectional"))
      (node (ref "X6") (pin "7") (pinfunction "7_7") (pintype "passive"))
    )
    (net (code "143") (name "SDA") (class "Default")
      (node (ref "IC2") (pin "11") (pinfunction "DIN_11") (pintype "bidirectional"))
      (node (ref "X6") (pin "8") (pinfunction "8_8") (pintype "passive"))
    )
    (net (code "144") (name "unconnected-(U$2-Pad2)") (class "Default")
      (node (ref "U$2") (pin "2") (pinfunction "2_2") (pintype "passive"))
    )
    (net (code "145") (name "unconnected-(U$2-Pad4)") (class "Default")
      (node (ref "U$2") (pin "4") (pinfunction "4_4") (pintype "passive"))
    )
    (net (code "146") (name "unconnected-(U$2-Pad6)") (class "Default")
      (node (ref "U$2") (pin "6") (pinfunction "6_6") (pintype "passive"))
    )
    (net (code "147") (name "unconnected-(U$2-Pad8)") (class "Default")
      (node (ref "U$2") (pin "8") (pinfunction "8_8") (pintype "passive"))
    )
    (net (code "148") (name "unconnected-(U$2-Pad10)") (class "Default")
      (node (ref "U$2") (pin "10") (pinfunction "10_10") (pintype "passive"))
    )
    (net (code "149") (name "unconnected-(U$2-Pad12)") (class "Default")
      (node (ref "U$2") (pin "12") (pinfunction "12_12") (pintype "passive"))
    )
    (net (code "150") (name "unconnected-(U$2-Pad14)") (class "Default")
      (node (ref "U$2") (pin "14") (pinfunction "14_14") (pintype "passive"))
    )
    (net (code "151") (name "unconnected-(U$2-Pad16)") (class "Default")
      (node (ref "U$2") (pin "16") (pinfunction "16_16") (pintype "passive"))
    )
    (net (code "152") (name "unconnected-(U$2-Pad18)") (class "Default")
      (node (ref "U$2") (pin "18") (pinfunction "18_18") (pintype "passive"))
    )
    (net (code "153") (name "unconnected-(U$2-Pad20)") (class "Default")
      (node (ref "U$2") (pin "20") (pinfunction "20_20") (pintype "passive"))
    )
    (net (code "154") (name "unconnected-(U$2-Pad22)") (class "Default")
      (node (ref "U$2") (pin "22") (pinfunction "22_22") (pintype "passive"))
    )
    (net (code "155") (name "unconnected-(U$2-Pad24)") (class "Default")
      (node (ref "U$2") (pin "24") (pinfunction "24_24") (pintype "passive"))
    )
    (net (code "156") (name "unconnected-(U$2-Pad26)") (class "Default")
      (node (ref "U$2") (pin "26") (pinfunction "26_26") (pintype "passive"))
    )
    (net (code "157") (name "unconnected-(U$2-Pad28)") (class "Default")
      (node (ref "U$2") (pin "28") (pinfunction "28_28") (pintype "passive"))
    )
    (net (code "158") (name "unconnected-(U$2-Pad30)") (class "Default")
      (node (ref "U$2") (pin "30") (pinfunction "30_30") (pintype "passive"))
    )
    (net (code "159") (name "unconnected-(U$3-Pad2)") (class "Default")
      (node (ref "U$3") (pin "2") (pinfunction "2_2") (pintype "passive"))
    )
    (net (code "160") (name "unconnected-(U$3-Pad4)") (class "Default")
      (node (ref "U$3") (pin "4") (pinfunction "4_4") (pintype "passive"))
    )
    (net (code "161") (name "unconnected-(U$3-Pad6)") (class "Default")
      (node (ref "U$3") (pin "6") (pinfunction "6_6") (pintype "passive"))
    )
    (net (code "162") (name "unconnected-(U$3-Pad8)") (class "Default")
      (node (ref "U$3") (pin "8") (pinfunction "8_8") (pintype "passive"))
    )
    (net (code "163") (name "unconnected-(U$3-Pad10)") (class "Default")
      (node (ref "U$3") (pin "10") (pinfunction "10_10") (pintype "passive"))
    )
    (net (code "164") (name "unconnected-(U$3-Pad12)") (class "Default")
      (node (ref "U$3") (pin "12") (pinfunction "12_12") (pintype "passive"))
    )
    (net (code "165") (name "unconnected-(U$3-Pad14)") (class "Default")
      (node (ref "U$3") (pin "14") (pinfunction "14_14") (pintype "passive"))
    )
    (net (code "166") (name "unconnected-(U$3-Pad16)") (class "Default")
      (node (ref "U$3") (pin "16") (pinfunction "16_16") (pintype "passive"))
    )
    (net (code "167") (name "unconnected-(U$3-Pad18)") (class "Default")
      (node (ref "U$3") (pin "18") (pinfunction "18_18") (pintype "passive"))
    )
    (net (code "168") (name "unconnected-(U$3-Pad20)") (class "Default")
      (node (ref "U$3") (pin "20") (pinfunction "20_20") (pintype "passive"))
    )
    (net (code "169") (name "unconnected-(U$3-Pad22)") (class "Default")
      (node (ref "U$3") (pin "22") (pinfunction "22_22") (pintype "passive"))
    )
    (net (code "170") (name "unconnected-(U$3-Pad24)") (class "Default")
      (node (ref "U$3") (pin "24") (pinfunction "24_24") (pintype "passive"))
    )
    (net (code "171") (name "unconnected-(U$3-Pad26)") (class "Default")
      (node (ref "U$3") (pin "26") (pinfunction "26_26") (pintype "passive"))
    )
    (net (code "172") (name "unconnected-(U$3-Pad28)") (class "Default")
      (node (ref "U$3") (pin "28") (pinfunction "28_28") (pintype "passive"))
    )
    (net (code "173") (name "unconnected-(U$3-Pad30)") (class "Default")
      (node (ref "U$3") (pin "30") (pinfunction "30_30") (pintype "passive"))
    )
    (net (code "174") (name "unconnected-(U$4-Pad2)") (class "Default")
      (node (ref "U$4") (pin "2") (pinfunction "2_2") (pintype "passive"))
    )
    (net (code "175") (name "unconnected-(U$4-Pad4)") (class "Default")
      (node (ref "U$4") (pin "4") (pinfunction "4_4") (pintype "passive"))
    )
    (net (code "176") (name "unconnected-(U$4-Pad6)") (class "Default")
      (node (ref "U$4") (pin "6") (pinfunction "6_6") (pintype "passive"))
    )
    (net (code "177") (name "unconnected-(U$4-Pad8)") (class "Default")
      (node (ref "U$4") (pin "8") (pinfunction "8_8") (pintype "passive"))
    )
    (net (code "178") (name "unconnected-(U$4-Pad10)") (class "Default")
      (node (ref "U$4") (pin "10") (pinfunction "10_10") (pintype "passive"))
    )
    (net (code "179") (name "unconnected-(U$4-Pad12)") (class "Default")
      (node (ref "U$4") (pin "12") (pinfunction "12_12") (pintype "passive"))
    )
    (net (code "180") (name "unconnected-(U$4-Pad14)") (class "Default")
      (node (ref "U$4") (pin "14") (pinfunction "14_14") (pintype "passive"))
    )
    (net (code "181") (name "unconnected-(U$4-Pad16)") (class "Default")
      (node (ref "U$4") (pin "16") (pinfunction "16_16") (pintype "passive"))
    )
    (net (code "182") (name "unconnected-(U$4-Pad18)") (class "Default")
      (node (ref "U$4") (pin "18") (pinfunction "18_18") (pintype "passive"))
    )
    (net (code "183") (name "unconnected-(U$4-Pad20)") (class "Default")
      (node (ref "U$4") (pin "20") (pinfunction "20_20") (pintype "passive"))
    )
    (net (code "184") (name "unconnected-(U$4-Pad22)") (class "Default")
      (node (ref "U$4") (pin "22") (pinfunction "22_22") (pintype "passive"))
    )
    (net (code "185") (name "unconnected-(U$4-Pad24)") (class "Default")
      (node (ref "U$4") (pin "24") (pinfunction "24_24") (pintype "passive"))
    )
    (net (code "186") (name "unconnected-(U$4-Pad26)") (class "Default")
      (node (ref "U$4") (pin "26") (pinfunction "26_26") (pintype "passive"))
    )
    (net (code "187") (name "unconnected-(U$4-Pad28)") (class "Default")
      (node (ref "U$4") (pin "28") (pinfunction "28_28") (pintype "passive"))
    )
    (net (code "188") (name "unconnected-(U$4-Pad30)") (class "Default")
      (node (ref "U$4") (pin "30") (pinfunction "30_30") (pintype "passive"))
    )
    (net (code "189") (name "unconnected-(X6-Pad5)") (class "Default")
      (node (ref "X6") (pin "5") (pinfunction "5_5") (pintype "passive"))
    )
    (net (code "190") (name "unconnected-(X6-Pad12)") (class "Default")
      (node (ref "X6") (pin "12") (pinfunction "12_12") (pintype "passive"))
    )
    (net (code "191") (name "unconnected-(X6-Pad13)") (class "Default")
      (node (ref "X6") (pin "13") (pinfunction "13_13") (pintype "passive"))
    )
    (net (code "192") (name "unconnected-(X10-Pad2)") (class "Default")
      (node (ref "X10") (pin "2") (pinfunction "2_2") (pintype "passive"))
    )
    (net (code "193") (name "unconnected-(X10-Pad4)") (class "Default")
      (node (ref "X10") (pin "4") (pinfunction "4_4") (pintype "passive"))
    )
    (net (code "194") (name "unconnected-(X10-Pad6)") (class "Default")
      (node (ref "X10") (pin "6") (pinfunction "6_6") (pintype "passive"))
    )
    (net (code "195") (name "unconnected-(X10-Pad8)") (class "Default")
      (node (ref "X10") (pin "8") (pinfunction "8_8") (pintype "passive"))
    )
    (net (code "196") (name "unconnected-(X10-Pad10)") (class "Default")
      (node (ref "X10") (pin "10") (pinfunction "10_10") (pintype "passive"))
    )
    (net (code "197") (name "unconnected-(X10-Pad12)") (class "Default")
      (node (ref "X10") (pin "12") (pinfunction "12_12") (pintype "passive"))
    )
    (net (code "198") (name "unconnected-(X10-Pad14)") (class "Default")
      (node (ref "X10") (pin "14") (pinfunction "14_14") (pintype "passive"))
    )
    (net (code "199") (name "~{SYNC}") (class "Default")
      (node (ref "IC2") (pin "9") (pinfunction "~{SYNC}_9") (pintype "bidirectional"))
      (node (ref "X6") (pin "10") (pinfunction "10_10") (pintype "passive"))
    )
  )
)
